# DDR3.net
KiCad netlist of a schematic drawn in Altium Designer
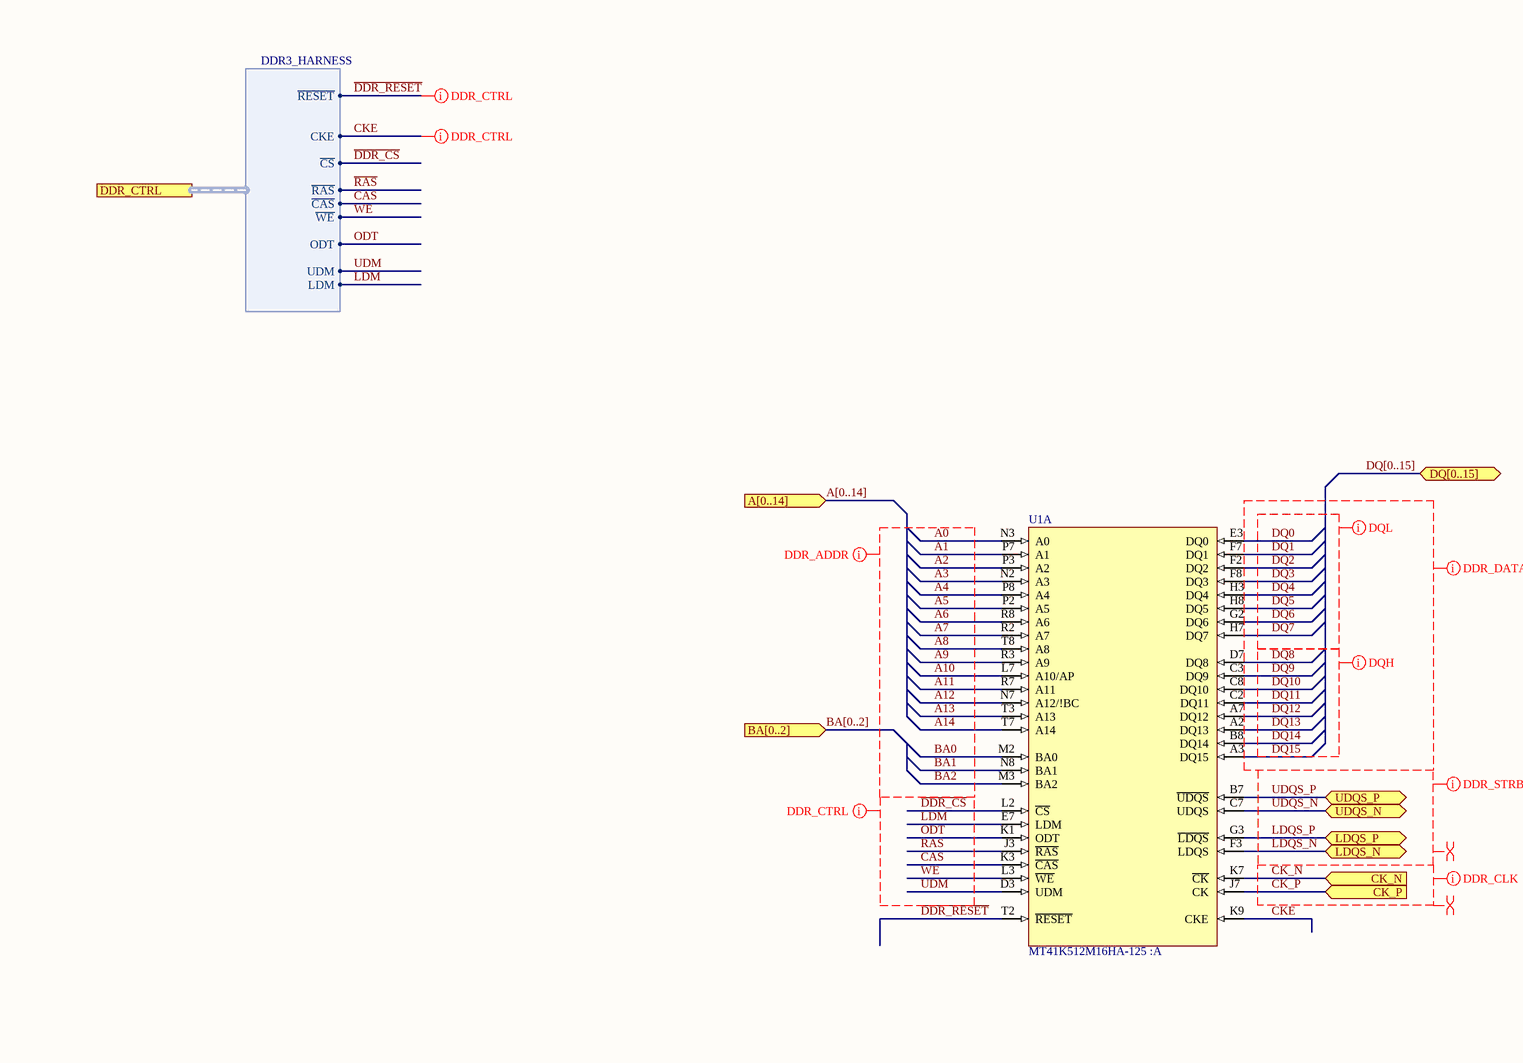
[diagram p0: DDR3.SchDoc, top left]
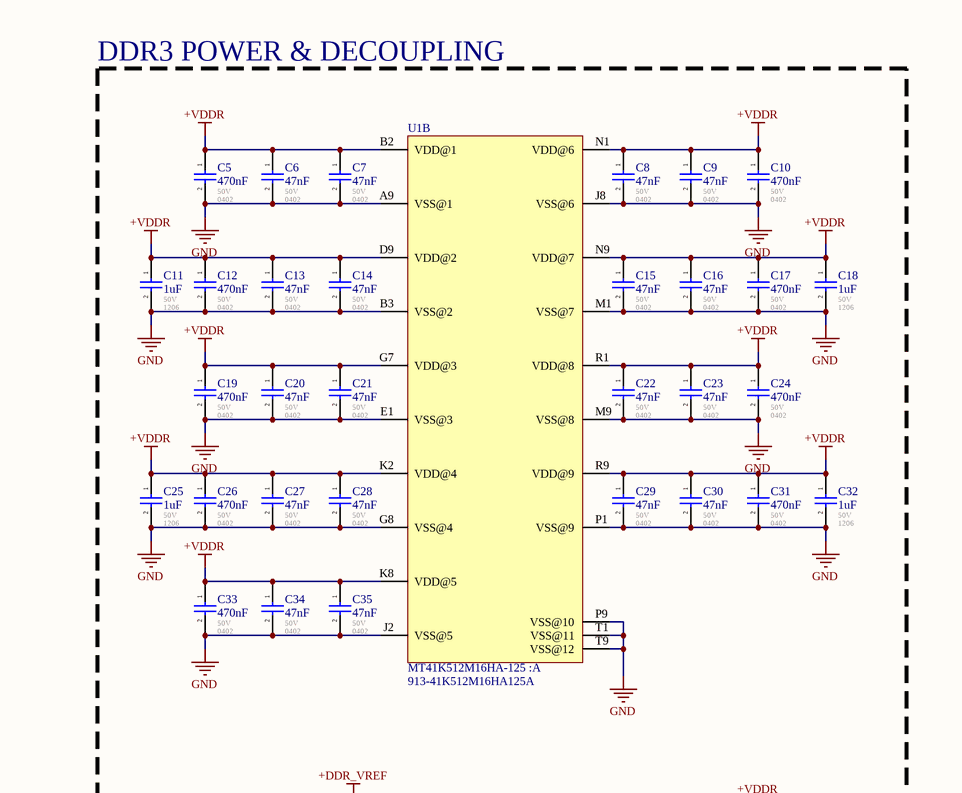
[diagram p1: DDR3.SchDoc, top right]
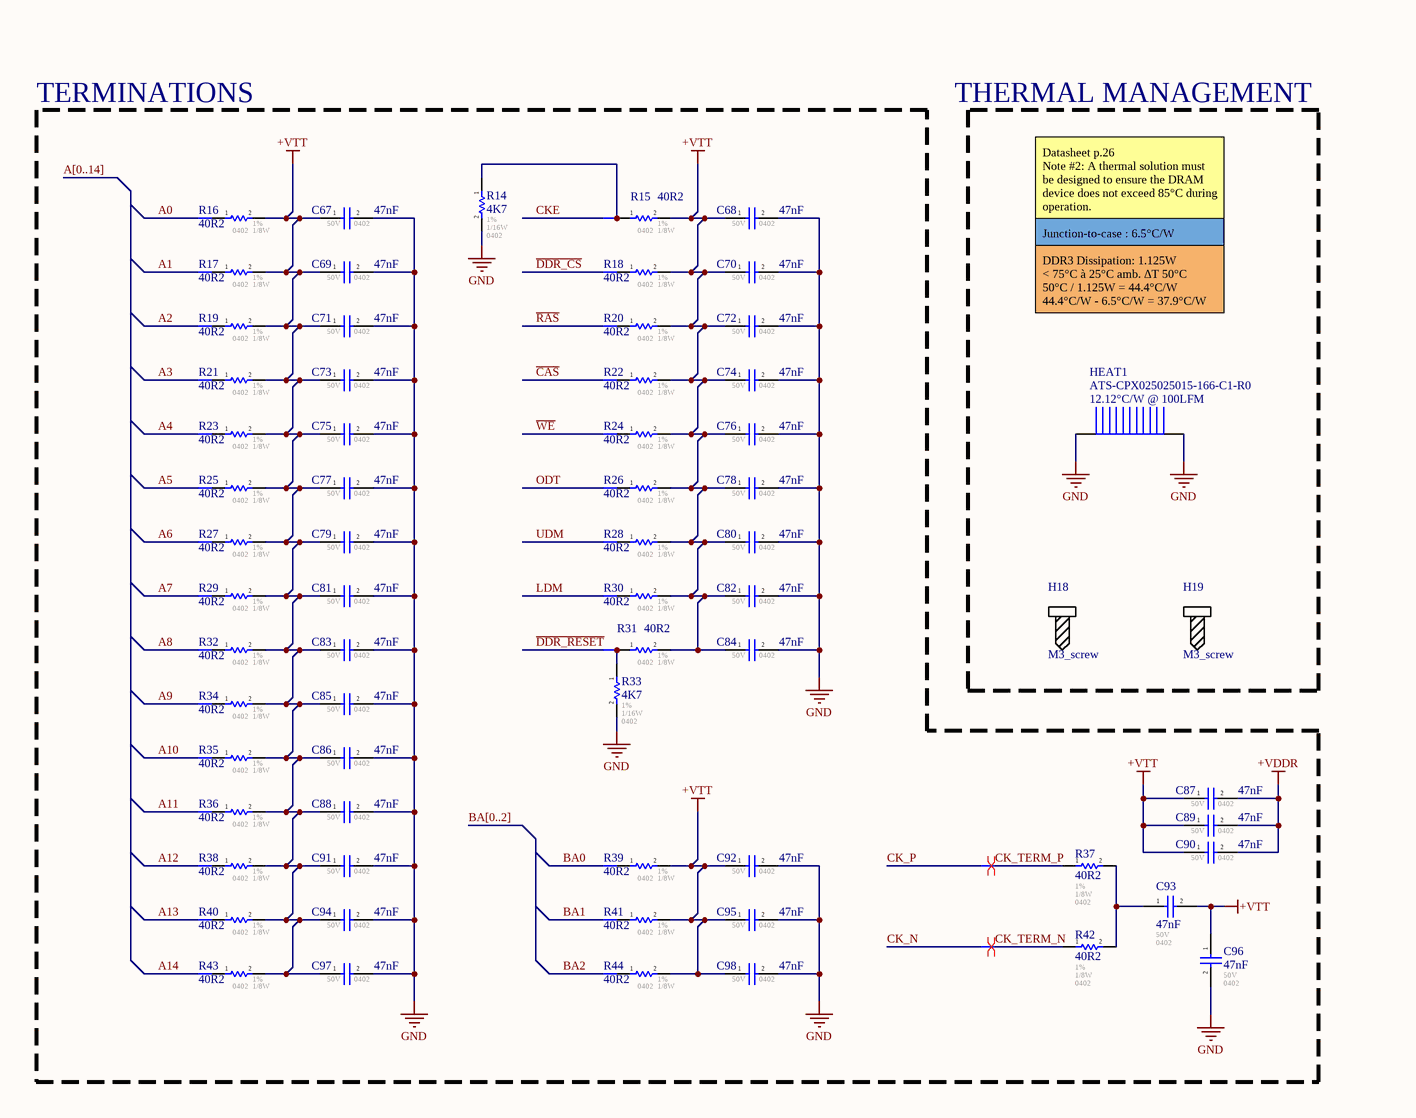
[diagram p2: DDR3.SchDoc, bottom left]
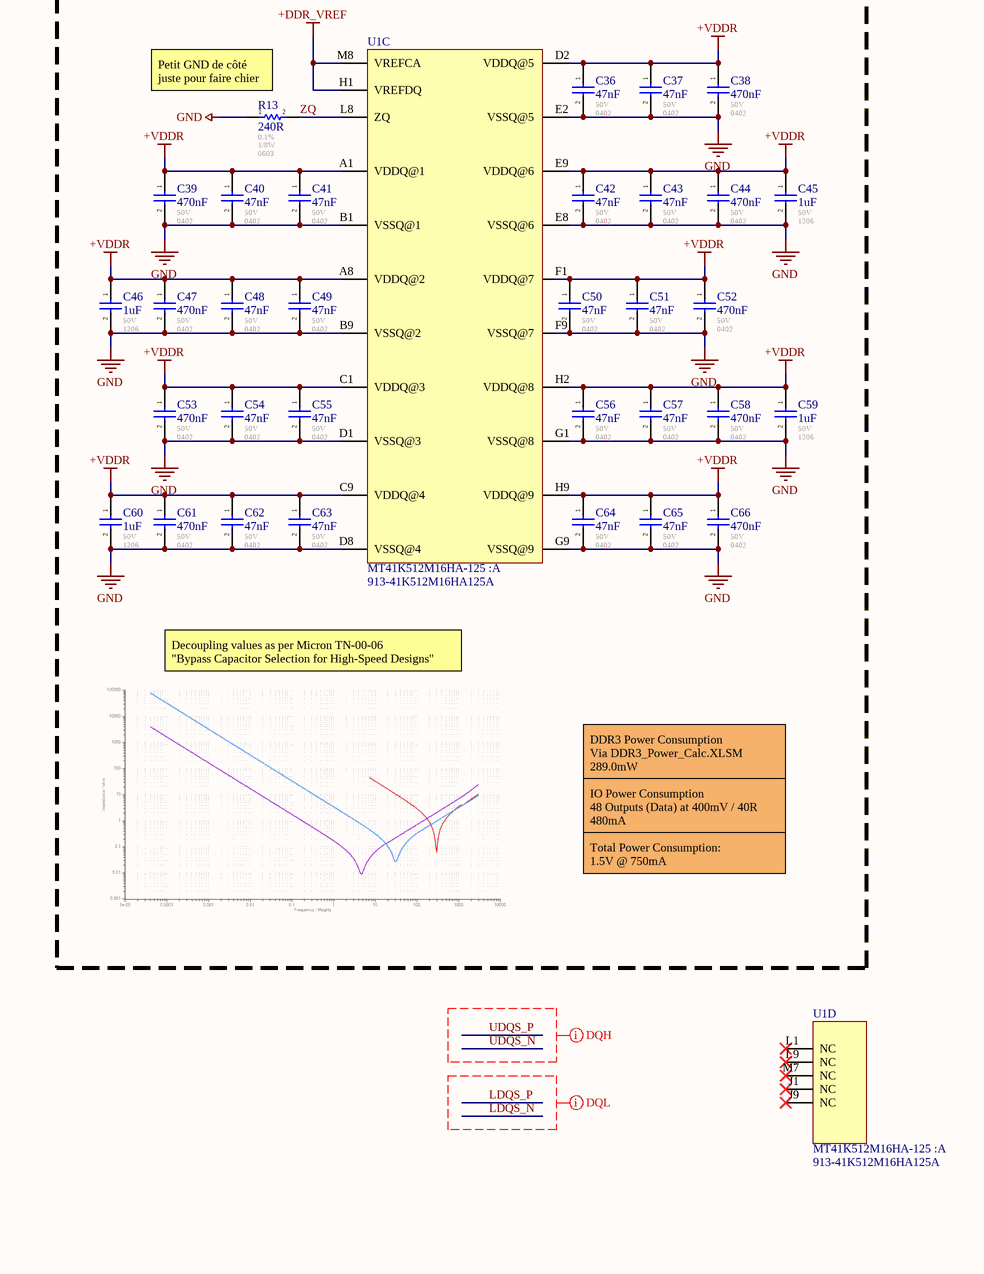
[diagram p3: DDR3.SchDoc, bottom right]

(export (version "E")
  (design (tool "Eeschema 10.0.6"))
  (components
    (comp (ref "C5")
      (value "470nF")
      (footprint "0402")
      (description "CGA3E3X7R1H474K080AB\r\n0603 470nF 10% X7R Ceramic Capacitor")
      (fields
        (field (name "MFR") "TDK")
        (field (name "PART#") "CGA3E3X7R1H474K080AB")
        (field (name "VOLTAGE - RATED") "50V")
      )
      (libsource (lib "Symbols") (part "CAP_CER"))
    )
    (comp (ref "C6")
      (value "47nF")
      (footprint "0402")
      (description "GCM155R71H473KE02J\r\n0402 47nF 10% X7R Ceramic Capacitor")
      (fields
        (field (name "MFR") "Murata")
        (field (name "PART#") "GCM155R71H473KE02J")
        (field (name "VOLTAGE - RATED") "50V")
      )
      (libsource (lib "Symbols") (part "CAP_CER"))
    )
    (comp (ref "C7")
      (value "47nF")
      (footprint "0402")
      (description "GCM155R71H473KE02J\r\n0402 47nF 10% X7R Ceramic Capacitor")
      (fields
        (field (name "MFR") "Murata")
        (field (name "PART#") "GCM155R71H473KE02J")
        (field (name "VOLTAGE - RATED") "50V")
      )
      (libsource (lib "Symbols") (part "CAP_CER"))
    )
    (comp (ref "C8")
      (value "47nF")
      (footprint "0402")
      (description "GCM155R71H473KE02J\r\n0402 47nF 10% X7R Ceramic Capacitor")
      (fields
        (field (name "MFR") "Murata")
        (field (name "PART#") "GCM155R71H473KE02J")
        (field (name "VOLTAGE - RATED") "50V")
      )
      (libsource (lib "Symbols") (part "CAP_CER"))
    )
    (comp (ref "C9")
      (value "47nF")
      (footprint "0402")
      (description "GCM155R71H473KE02J\r\n0402 47nF 10% X7R Ceramic Capacitor")
      (fields
        (field (name "MFR") "Murata")
        (field (name "PART#") "GCM155R71H473KE02J")
        (field (name "VOLTAGE - RATED") "50V")
      )
      (libsource (lib "Symbols") (part "CAP_CER"))
    )
    (comp (ref "C10")
      (value "470nF")
      (footprint "0402")
      (description "CGA3E3X7R1H474K080AB\r\n0603 470nF 10% X7R Ceramic Capacitor")
      (fields
        (field (name "MFR") "TDK")
        (field (name "PART#") "CGA3E3X7R1H474K080AB")
        (field (name "VOLTAGE - RATED") "50V")
      )
      (libsource (lib "Symbols") (part "CAP_CER"))
    )
    (comp (ref "C11")
      (value "1uF")
      (footprint "1206")
      (description "GCJ31CR71H105KA12L\r\n1206 1uF 10% X7R Ceramic Capacitor")
      (fields
        (field (name "MFR") "Murata")
        (field (name "PART#") "GCJ31CR71H105KA12L")
        (field (name "VOLTAGE - RATED") "50V")
      )
      (libsource (lib "Symbols") (part "CAP_CER"))
    )
    (comp (ref "C12")
      (value "470nF")
      (footprint "0402")
      (description "CGA3E3X7R1H474K080AB\r\n0603 470nF 10% X7R Ceramic Capacitor")
      (fields
        (field (name "MFR") "TDK")
        (field (name "PART#") "CGA3E3X7R1H474K080AB")
        (field (name "VOLTAGE - RATED") "50V")
      )
      (libsource (lib "Symbols") (part "CAP_CER"))
    )
    (comp (ref "C13")
      (value "47nF")
      (footprint "0402")
      (description "GCM155R71H473KE02J\r\n0402 47nF 10% X7R Ceramic Capacitor")
      (fields
        (field (name "MFR") "Murata")
        (field (name "PART#") "GCM155R71H473KE02J")
        (field (name "VOLTAGE - RATED") "50V")
      )
      (libsource (lib "Symbols") (part "CAP_CER"))
    )
    (comp (ref "C14")
      (value "47nF")
      (footprint "0402")
      (description "GCM155R71H473KE02J\r\n0402 47nF 10% X7R Ceramic Capacitor")
      (fields
        (field (name "MFR") "Murata")
        (field (name "PART#") "GCM155R71H473KE02J")
        (field (name "VOLTAGE - RATED") "50V")
      )
      (libsource (lib "Symbols") (part "CAP_CER"))
    )
    (comp (ref "C15")
      (value "47nF")
      (footprint "0402")
      (description "GCM155R71H473KE02J\r\n0402 47nF 10% X7R Ceramic Capacitor")
      (fields
        (field (name "MFR") "Murata")
        (field (name "PART#") "GCM155R71H473KE02J")
        (field (name "VOLTAGE - RATED") "50V")
      )
      (libsource (lib "Symbols") (part "CAP_CER"))
    )
    (comp (ref "C16")
      (value "47nF")
      (footprint "0402")
      (description "GCM155R71H473KE02J\r\n0402 47nF 10% X7R Ceramic Capacitor")
      (fields
        (field (name "MFR") "Murata")
        (field (name "PART#") "GCM155R71H473KE02J")
        (field (name "VOLTAGE - RATED") "50V")
      )
      (libsource (lib "Symbols") (part "CAP_CER"))
    )
    (comp (ref "C17")
      (value "470nF")
      (footprint "0402")
      (description "CGA3E3X7R1H474K080AB\r\n0603 470nF 10% X7R Ceramic Capacitor")
      (fields
        (field (name "MFR") "TDK")
        (field (name "PART#") "CGA3E3X7R1H474K080AB")
        (field (name "VOLTAGE - RATED") "50V")
      )
      (libsource (lib "Symbols") (part "CAP_CER"))
    )
    (comp (ref "C18")
      (value "1uF")
      (footprint "1206")
      (description "GCJ31CR71H105KA12L\r\n1206 1uF 10% X7R Ceramic Capacitor")
      (fields
        (field (name "MFR") "Murata")
        (field (name "PART#") "GCJ31CR71H105KA12L")
        (field (name "VOLTAGE - RATED") "50V")
      )
      (libsource (lib "Symbols") (part "CAP_CER"))
    )
    (comp (ref "C19")
      (value "470nF")
      (footprint "0402")
      (description "CGA3E3X7R1H474K080AB\r\n0603 470nF 10% X7R Ceramic Capacitor")
      (fields
        (field (name "MFR") "TDK")
        (field (name "PART#") "CGA3E3X7R1H474K080AB")
        (field (name "VOLTAGE - RATED") "50V")
      )
      (libsource (lib "Symbols") (part "CAP_CER"))
    )
    (comp (ref "C20")
      (value "47nF")
      (footprint "0402")
      (description "GCM155R71H473KE02J\r\n0402 47nF 10% X7R Ceramic Capacitor")
      (fields
        (field (name "MFR") "Murata")
        (field (name "PART#") "GCM155R71H473KE02J")
        (field (name "VOLTAGE - RATED") "50V")
      )
      (libsource (lib "Symbols") (part "CAP_CER"))
    )
    (comp (ref "C21")
      (value "47nF")
      (footprint "0402")
      (description "GCM155R71H473KE02J\r\n0402 47nF 10% X7R Ceramic Capacitor")
      (fields
        (field (name "MFR") "Murata")
        (field (name "PART#") "GCM155R71H473KE02J")
        (field (name "VOLTAGE - RATED") "50V")
      )
      (libsource (lib "Symbols") (part "CAP_CER"))
    )
    (comp (ref "C22")
      (value "47nF")
      (footprint "0402")
      (description "GCM155R71H473KE02J\r\n0402 47nF 10% X7R Ceramic Capacitor")
      (fields
        (field (name "MFR") "Murata")
        (field (name "PART#") "GCM155R71H473KE02J")
        (field (name "VOLTAGE - RATED") "50V")
      )
      (libsource (lib "Symbols") (part "CAP_CER"))
    )
    (comp (ref "C23")
      (value "47nF")
      (footprint "0402")
      (description "GCM155R71H473KE02J\r\n0402 47nF 10% X7R Ceramic Capacitor")
      (fields
        (field (name "MFR") "Murata")
        (field (name "PART#") "GCM155R71H473KE02J")
        (field (name "VOLTAGE - RATED") "50V")
      )
      (libsource (lib "Symbols") (part "CAP_CER"))
    )
    (comp (ref "C24")
      (value "470nF")
      (footprint "0402")
      (description "CGA3E3X7R1H474K080AB\r\n0603 470nF 10% X7R Ceramic Capacitor")
      (fields
        (field (name "MFR") "TDK")
        (field (name "PART#") "CGA3E3X7R1H474K080AB")
        (field (name "VOLTAGE - RATED") "50V")
      )
      (libsource (lib "Symbols") (part "CAP_CER"))
    )
    (comp (ref "C25")
      (value "1uF")
      (footprint "1206")
      (description "GCJ31CR71H105KA12L\r\n1206 1uF 10% X7R Ceramic Capacitor")
      (fields
        (field (name "MFR") "Murata")
        (field (name "PART#") "GCJ31CR71H105KA12L")
        (field (name "VOLTAGE - RATED") "50V")
      )
      (libsource (lib "Symbols") (part "CAP_CER"))
    )
    (comp (ref "C26")
      (value "470nF")
      (footprint "0402")
      (description "CGA3E3X7R1H474K080AB\r\n0603 470nF 10% X7R Ceramic Capacitor")
      (fields
        (field (name "MFR") "TDK")
        (field (name "PART#") "CGA3E3X7R1H474K080AB")
        (field (name "VOLTAGE - RATED") "50V")
      )
      (libsource (lib "Symbols") (part "CAP_CER"))
    )
    (comp (ref "C27")
      (value "47nF")
      (footprint "0402")
      (description "GCM155R71H473KE02J\r\n0402 47nF 10% X7R Ceramic Capacitor")
      (fields
        (field (name "MFR") "Murata")
        (field (name "PART#") "GCM155R71H473KE02J")
        (field (name "VOLTAGE - RATED") "50V")
      )
      (libsource (lib "Symbols") (part "CAP_CER"))
    )
    (comp (ref "C28")
      (value "47nF")
      (footprint "0402")
      (description "GCM155R71H473KE02J\r\n0402 47nF 10% X7R Ceramic Capacitor")
      (fields
        (field (name "MFR") "Murata")
        (field (name "PART#") "GCM155R71H473KE02J")
        (field (name "VOLTAGE - RATED") "50V")
      )
      (libsource (lib "Symbols") (part "CAP_CER"))
    )
    (comp (ref "C29")
      (value "47nF")
      (footprint "0402")
      (description "GCM155R71H473KE02J\r\n0402 47nF 10% X7R Ceramic Capacitor")
      (fields
        (field (name "MFR") "Murata")
        (field (name "PART#") "GCM155R71H473KE02J")
        (field (name "VOLTAGE - RATED") "50V")
      )
      (libsource (lib "Symbols") (part "CAP_CER"))
    )
    (comp (ref "C30")
      (value "47nF")
      (footprint "0402")
      (description "GCM155R71H473KE02J\r\n0402 47nF 10% X7R Ceramic Capacitor")
      (fields
        (field (name "MFR") "Murata")
        (field (name "PART#") "GCM155R71H473KE02J")
        (field (name "VOLTAGE - RATED") "50V")
      )
      (libsource (lib "Symbols") (part "CAP_CER"))
    )
    (comp (ref "C31")
      (value "470nF")
      (footprint "0402")
      (description "CGA3E3X7R1H474K080AB\r\n0603 470nF 10% X7R Ceramic Capacitor")
      (fields
        (field (name "MFR") "TDK")
        (field (name "PART#") "CGA3E3X7R1H474K080AB")
        (field (name "VOLTAGE - RATED") "50V")
      )
      (libsource (lib "Symbols") (part "CAP_CER"))
    )
    (comp (ref "C32")
      (value "1uF")
      (footprint "1206")
      (description "GCJ31CR71H105KA12L\r\n1206 1uF 10% X7R Ceramic Capacitor")
      (fields
        (field (name "MFR") "Murata")
        (field (name "PART#") "GCJ31CR71H105KA12L")
        (field (name "VOLTAGE - RATED") "50V")
      )
      (libsource (lib "Symbols") (part "CAP_CER"))
    )
    (comp (ref "C33")
      (value "470nF")
      (footprint "0402")
      (description "CGA3E3X7R1H474K080AB\r\n0603 470nF 10% X7R Ceramic Capacitor")
      (fields
        (field (name "MFR") "TDK")
        (field (name "PART#") "CGA3E3X7R1H474K080AB")
        (field (name "VOLTAGE - RATED") "50V")
      )
      (libsource (lib "Symbols") (part "CAP_CER"))
    )
    (comp (ref "C34")
      (value "47nF")
      (footprint "0402")
      (description "GCM155R71H473KE02J\r\n0402 47nF 10% X7R Ceramic Capacitor")
      (fields
        (field (name "MFR") "Murata")
        (field (name "PART#") "GCM155R71H473KE02J")
        (field (name "VOLTAGE - RATED") "50V")
      )
      (libsource (lib "Symbols") (part "CAP_CER"))
    )
    (comp (ref "C35")
      (value "47nF")
      (footprint "0402")
      (description "GCM155R71H473KE02J\r\n0402 47nF 10% X7R Ceramic Capacitor")
      (fields
        (field (name "MFR") "Murata")
        (field (name "PART#") "GCM155R71H473KE02J")
        (field (name "VOLTAGE - RATED") "50V")
      )
      (libsource (lib "Symbols") (part "CAP_CER"))
    )
    (comp (ref "C36")
      (value "47nF")
      (footprint "0402")
      (description "GCM155R71H473KE02J\r\n0402 47nF 10% X7R Ceramic Capacitor")
      (fields
        (field (name "MFR") "Murata")
        (field (name "PART#") "GCM155R71H473KE02J")
        (field (name "VOLTAGE - RATED") "50V")
      )
      (libsource (lib "Symbols") (part "CAP_CER"))
    )
    (comp (ref "C37")
      (value "47nF")
      (footprint "0402")
      (description "GCM155R71H473KE02J\r\n0402 47nF 10% X7R Ceramic Capacitor")
      (fields
        (field (name "MFR") "Murata")
        (field (name "PART#") "GCM155R71H473KE02J")
        (field (name "VOLTAGE - RATED") "50V")
      )
      (libsource (lib "Symbols") (part "CAP_CER"))
    )
    (comp (ref "C38")
      (value "470nF")
      (footprint "0402")
      (description "CGA3E3X7R1H474K080AB\r\n0603 470nF 10% X7R Ceramic Capacitor")
      (fields
        (field (name "MFR") "TDK")
        (field (name "PART#") "CGA3E3X7R1H474K080AB")
        (field (name "VOLTAGE - RATED") "50V")
      )
      (libsource (lib "Symbols") (part "CAP_CER"))
    )
    (comp (ref "C39")
      (value "470nF")
      (footprint "0402")
      (description "CGA3E3X7R1H474K080AB\r\n0603 470nF 10% X7R Ceramic Capacitor")
      (fields
        (field (name "MFR") "TDK")
        (field (name "PART#") "CGA3E3X7R1H474K080AB")
        (field (name "VOLTAGE - RATED") "50V")
      )
      (libsource (lib "Symbols") (part "CAP_CER"))
    )
    (comp (ref "C40")
      (value "47nF")
      (footprint "0402")
      (description "GCM155R71H473KE02J\r\n0402 47nF 10% X7R Ceramic Capacitor")
      (fields
        (field (name "MFR") "Murata")
        (field (name "PART#") "GCM155R71H473KE02J")
        (field (name "VOLTAGE - RATED") "50V")
      )
      (libsource (lib "Symbols") (part "CAP_CER"))
    )
    (comp (ref "C41")
      (value "47nF")
      (footprint "0402")
      (description "GCM155R71H473KE02J\r\n0402 47nF 10% X7R Ceramic Capacitor")
      (fields
        (field (name "MFR") "Murata")
        (field (name "PART#") "GCM155R71H473KE02J")
        (field (name "VOLTAGE - RATED") "50V")
      )
      (libsource (lib "Symbols") (part "CAP_CER"))
    )
    (comp (ref "C42")
      (value "47nF")
      (footprint "0402")
      (description "GCM155R71H473KE02J\r\n0402 47nF 10% X7R Ceramic Capacitor")
      (fields
        (field (name "MFR") "Murata")
        (field (name "PART#") "GCM155R71H473KE02J")
        (field (name "VOLTAGE - RATED") "50V")
      )
      (libsource (lib "Symbols") (part "CAP_CER"))
    )
    (comp (ref "C43")
      (value "47nF")
      (footprint "0402")
      (description "GCM155R71H473KE02J\r\n0402 47nF 10% X7R Ceramic Capacitor")
      (fields
        (field (name "MFR") "Murata")
        (field (name "PART#") "GCM155R71H473KE02J")
        (field (name "VOLTAGE - RATED") "50V")
      )
      (libsource (lib "Symbols") (part "CAP_CER"))
    )
    (comp (ref "C44")
      (value "470nF")
      (footprint "0402")
      (description "CGA3E3X7R1H474K080AB\r\n0603 470nF 10% X7R Ceramic Capacitor")
      (fields
        (field (name "MFR") "TDK")
        (field (name "PART#") "CGA3E3X7R1H474K080AB")
        (field (name "VOLTAGE - RATED") "50V")
      )
      (libsource (lib "Symbols") (part "CAP_CER"))
    )
    (comp (ref "C45")
      (value "1uF")
      (footprint "1206")
      (description "GCJ31CR71H105KA12L\r\n1206 1uF 10% X7R Ceramic Capacitor")
      (fields
        (field (name "MFR") "Murata")
        (field (name "PART#") "GCJ31CR71H105KA12L")
        (field (name "VOLTAGE - RATED") "50V")
      )
      (libsource (lib "Symbols") (part "CAP_CER"))
    )
    (comp (ref "C46")
      (value "1uF")
      (footprint "1206")
      (description "GCJ31CR71H105KA12L\r\n1206 1uF 10% X7R Ceramic Capacitor")
      (fields
        (field (name "MFR") "Murata")
        (field (name "PART#") "GCJ31CR71H105KA12L")
        (field (name "VOLTAGE - RATED") "50V")
      )
      (libsource (lib "Symbols") (part "CAP_CER"))
    )
    (comp (ref "C47")
      (value "470nF")
      (footprint "0402")
      (description "CGA3E3X7R1H474K080AB\r\n0603 470nF 10% X7R Ceramic Capacitor")
      (fields
        (field (name "MFR") "TDK")
        (field (name "PART#") "CGA3E3X7R1H474K080AB")
        (field (name "VOLTAGE - RATED") "50V")
      )
      (libsource (lib "Symbols") (part "CAP_CER"))
    )
    (comp (ref "C48")
      (value "47nF")
      (footprint "0402")
      (description "GCM155R71H473KE02J\r\n0402 47nF 10% X7R Ceramic Capacitor")
      (fields
        (field (name "MFR") "Murata")
        (field (name "PART#") "GCM155R71H473KE02J")
        (field (name "VOLTAGE - RATED") "50V")
      )
      (libsource (lib "Symbols") (part "CAP_CER"))
    )
    (comp (ref "C49")
      (value "47nF")
      (footprint "0402")
      (description "GCM155R71H473KE02J\r\n0402 47nF 10% X7R Ceramic Capacitor")
      (fields
        (field (name "MFR") "Murata")
        (field (name "PART#") "GCM155R71H473KE02J")
        (field (name "VOLTAGE - RATED") "50V")
      )
      (libsource (lib "Symbols") (part "CAP_CER"))
    )
    (comp (ref "C50")
      (value "47nF")
      (footprint "0402")
      (description "GCM155R71H473KE02J\r\n0402 47nF 10% X7R Ceramic Capacitor")
      (fields
        (field (name "MFR") "Murata")
        (field (name "PART#") "GCM155R71H473KE02J")
        (field (name "VOLTAGE - RATED") "50V")
      )
      (libsource (lib "Symbols") (part "CAP_CER"))
    )
    (comp (ref "C51")
      (value "47nF")
      (footprint "0402")
      (description "GCM155R71H473KE02J\r\n0402 47nF 10% X7R Ceramic Capacitor")
      (fields
        (field (name "MFR") "Murata")
        (field (name "PART#") "GCM155R71H473KE02J")
        (field (name "VOLTAGE - RATED") "50V")
      )
      (libsource (lib "Symbols") (part "CAP_CER"))
    )
    (comp (ref "C52")
      (value "470nF")
      (footprint "0402")
      (description "CGA3E3X7R1H474K080AB\r\n0603 470nF 10% X7R Ceramic Capacitor")
      (fields
        (field (name "MFR") "TDK")
        (field (name "PART#") "CGA3E3X7R1H474K080AB")
        (field (name "VOLTAGE - RATED") "50V")
      )
      (libsource (lib "Symbols") (part "CAP_CER"))
    )
    (comp (ref "C53")
      (value "470nF")
      (footprint "0402")
      (description "CGA3E3X7R1H474K080AB\r\n0603 470nF 10% X7R Ceramic Capacitor")
      (fields
        (field (name "MFR") "TDK")
        (field (name "PART#") "CGA3E3X7R1H474K080AB")
        (field (name "VOLTAGE - RATED") "50V")
      )
      (libsource (lib "Symbols") (part "CAP_CER"))
    )
    (comp (ref "C54")
      (value "47nF")
      (footprint "0402")
      (description "GCM155R71H473KE02J\r\n0402 47nF 10% X7R Ceramic Capacitor")
      (fields
        (field (name "MFR") "Murata")
        (field (name "PART#") "GCM155R71H473KE02J")
        (field (name "VOLTAGE - RATED") "50V")
      )
      (libsource (lib "Symbols") (part "CAP_CER"))
    )
    (comp (ref "C55")
      (value "47nF")
      (footprint "0402")
      (description "GCM155R71H473KE02J\r\n0402 47nF 10% X7R Ceramic Capacitor")
      (fields
        (field (name "MFR") "Murata")
        (field (name "PART#") "GCM155R71H473KE02J")
        (field (name "VOLTAGE - RATED") "50V")
      )
      (libsource (lib "Symbols") (part "CAP_CER"))
    )
    (comp (ref "C56")
      (value "47nF")
      (footprint "0402")
      (description "GCM155R71H473KE02J\r\n0402 47nF 10% X7R Ceramic Capacitor")
      (fields
        (field (name "MFR") "Murata")
        (field (name "PART#") "GCM155R71H473KE02J")
        (field (name "VOLTAGE - RATED") "50V")
      )
      (libsource (lib "Symbols") (part "CAP_CER"))
    )
    (comp (ref "C57")
      (value "47nF")
      (footprint "0402")
      (description "GCM155R71H473KE02J\r\n0402 47nF 10% X7R Ceramic Capacitor")
      (fields
        (field (name "MFR") "Murata")
        (field (name "PART#") "GCM155R71H473KE02J")
        (field (name "VOLTAGE - RATED") "50V")
      )
      (libsource (lib "Symbols") (part "CAP_CER"))
    )
    (comp (ref "C58")
      (value "470nF")
      (footprint "0402")
      (description "CGA3E3X7R1H474K080AB\r\n0603 470nF 10% X7R Ceramic Capacitor")
      (fields
        (field (name "MFR") "TDK")
        (field (name "PART#") "CGA3E3X7R1H474K080AB")
        (field (name "VOLTAGE - RATED") "50V")
      )
      (libsource (lib "Symbols") (part "CAP_CER"))
    )
    (comp (ref "C59")
      (value "1uF")
      (footprint "1206")
      (description "GCJ31CR71H105KA12L\r\n1206 1uF 10% X7R Ceramic Capacitor")
      (fields
        (field (name "MFR") "Murata")
        (field (name "PART#") "GCJ31CR71H105KA12L")
        (field (name "VOLTAGE - RATED") "50V")
      )
      (libsource (lib "Symbols") (part "CAP_CER"))
    )
    (comp (ref "C60")
      (value "1uF")
      (footprint "1206")
      (description "GCJ31CR71H105KA12L\r\n1206 1uF 10% X7R Ceramic Capacitor")
      (fields
        (field (name "MFR") "Murata")
        (field (name "PART#") "GCJ31CR71H105KA12L")
        (field (name "VOLTAGE - RATED") "50V")
      )
      (libsource (lib "Symbols") (part "CAP_CER"))
    )
    (comp (ref "C61")
      (value "470nF")
      (footprint "0402")
      (description "CGA3E3X7R1H474K080AB\r\n0603 470nF 10% X7R Ceramic Capacitor")
      (fields
        (field (name "MFR") "TDK")
        (field (name "PART#") "CGA3E3X7R1H474K080AB")
        (field (name "VOLTAGE - RATED") "50V")
      )
      (libsource (lib "Symbols") (part "CAP_CER"))
    )
    (comp (ref "C62")
      (value "47nF")
      (footprint "0402")
      (description "GCM155R71H473KE02J\r\n0402 47nF 10% X7R Ceramic Capacitor")
      (fields
        (field (name "MFR") "Murata")
        (field (name "PART#") "GCM155R71H473KE02J")
        (field (name "VOLTAGE - RATED") "50V")
      )
      (libsource (lib "Symbols") (part "CAP_CER"))
    )
    (comp (ref "C63")
      (value "47nF")
      (footprint "0402")
      (description "GCM155R71H473KE02J\r\n0402 47nF 10% X7R Ceramic Capacitor")
      (fields
        (field (name "MFR") "Murata")
        (field (name "PART#") "GCM155R71H473KE02J")
        (field (name "VOLTAGE - RATED") "50V")
      )
      (libsource (lib "Symbols") (part "CAP_CER"))
    )
    (comp (ref "C64")
      (value "47nF")
      (footprint "0402")
      (description "GCM155R71H473KE02J\r\n0402 47nF 10% X7R Ceramic Capacitor")
      (fields
        (field (name "MFR") "Murata")
        (field (name "PART#") "GCM155R71H473KE02J")
        (field (name "VOLTAGE - RATED") "50V")
      )
      (libsource (lib "Symbols") (part "CAP_CER"))
    )
    (comp (ref "C65")
      (value "47nF")
      (footprint "0402")
      (description "GCM155R71H473KE02J\r\n0402 47nF 10% X7R Ceramic Capacitor")
      (fields
        (field (name "MFR") "Murata")
        (field (name "PART#") "GCM155R71H473KE02J")
        (field (name "VOLTAGE - RATED") "50V")
      )
      (libsource (lib "Symbols") (part "CAP_CER"))
    )
    (comp (ref "C66")
      (value "470nF")
      (footprint "0402")
      (description "CGA3E3X7R1H474K080AB\r\n0603 470nF 10% X7R Ceramic Capacitor")
      (fields
        (field (name "MFR") "TDK")
        (field (name "PART#") "CGA3E3X7R1H474K080AB")
        (field (name "VOLTAGE - RATED") "50V")
      )
      (libsource (lib "Symbols") (part "CAP_CER"))
    )
    (comp (ref "C67")
      (value "47nF")
      (footprint "0402")
      (description "GCM155R71H473KE02J\r\n0402 47nF 10% X7R Ceramic Capacitor")
      (fields
        (field (name "MFR") "Murata")
        (field (name "PART#") "GCM155R71H473KE02J")
        (field (name "VOLTAGE - RATED") "50V")
      )
      (libsource (lib "Symbols") (part "CAP_CER"))
    )
    (comp (ref "C68")
      (value "47nF")
      (footprint "0402")
      (description "GCM155R71H473KE02J\r\n0402 47nF 10% X7R Ceramic Capacitor")
      (fields
        (field (name "MFR") "Murata")
        (field (name "PART#") "GCM155R71H473KE02J")
        (field (name "VOLTAGE - RATED") "50V")
      )
      (libsource (lib "Symbols") (part "CAP_CER"))
    )
    (comp (ref "C69")
      (value "47nF")
      (footprint "0402")
      (description "GCM155R71H473KE02J\r\n0402 47nF 10% X7R Ceramic Capacitor")
      (fields
        (field (name "MFR") "Murata")
        (field (name "PART#") "GCM155R71H473KE02J")
        (field (name "VOLTAGE - RATED") "50V")
      )
      (libsource (lib "Symbols") (part "CAP_CER"))
    )
    (comp (ref "C70")
      (value "47nF")
      (footprint "0402")
      (description "GCM155R71H473KE02J\r\n0402 47nF 10% X7R Ceramic Capacitor")
      (fields
        (field (name "MFR") "Murata")
        (field (name "PART#") "GCM155R71H473KE02J")
        (field (name "VOLTAGE - RATED") "50V")
      )
      (libsource (lib "Symbols") (part "CAP_CER"))
    )
    (comp (ref "C71")
      (value "47nF")
      (footprint "0402")
      (description "GCM155R71H473KE02J\r\n0402 47nF 10% X7R Ceramic Capacitor")
      (fields
        (field (name "MFR") "Murata")
        (field (name "PART#") "GCM155R71H473KE02J")
        (field (name "VOLTAGE - RATED") "50V")
      )
      (libsource (lib "Symbols") (part "CAP_CER"))
    )
    (comp (ref "C72")
      (value "47nF")
      (footprint "0402")
      (description "GCM155R71H473KE02J\r\n0402 47nF 10% X7R Ceramic Capacitor")
      (fields
        (field (name "MFR") "Murata")
        (field (name "PART#") "GCM155R71H473KE02J")
        (field (name "VOLTAGE - RATED") "50V")
      )
      (libsource (lib "Symbols") (part "CAP_CER"))
    )
    (comp (ref "C73")
      (value "47nF")
      (footprint "0402")
      (description "GCM155R71H473KE02J\r\n0402 47nF 10% X7R Ceramic Capacitor")
      (fields
        (field (name "MFR") "Murata")
        (field (name "PART#") "GCM155R71H473KE02J")
        (field (name "VOLTAGE - RATED") "50V")
      )
      (libsource (lib "Symbols") (part "CAP_CER"))
    )
    (comp (ref "C74")
      (value "47nF")
      (footprint "0402")
      (description "GCM155R71H473KE02J\r\n0402 47nF 10% X7R Ceramic Capacitor")
      (fields
        (field (name "MFR") "Murata")
        (field (name "PART#") "GCM155R71H473KE02J")
        (field (name "VOLTAGE - RATED") "50V")
      )
      (libsource (lib "Symbols") (part "CAP_CER"))
    )
    (comp (ref "C75")
      (value "47nF")
      (footprint "0402")
      (description "GCM155R71H473KE02J\r\n0402 47nF 10% X7R Ceramic Capacitor")
      (fields
        (field (name "MFR") "Murata")
        (field (name "PART#") "GCM155R71H473KE02J")
        (field (name "VOLTAGE - RATED") "50V")
      )
      (libsource (lib "Symbols") (part "CAP_CER"))
    )
    (comp (ref "C76")
      (value "47nF")
      (footprint "0402")
      (description "GCM155R71H473KE02J\r\n0402 47nF 10% X7R Ceramic Capacitor")
      (fields
        (field (name "MFR") "Murata")
        (field (name "PART#") "GCM155R71H473KE02J")
        (field (name "VOLTAGE - RATED") "50V")
      )
      (libsource (lib "Symbols") (part "CAP_CER"))
    )
    (comp (ref "C77")
      (value "47nF")
      (footprint "0402")
      (description "GCM155R71H473KE02J\r\n0402 47nF 10% X7R Ceramic Capacitor")
      (fields
        (field (name "MFR") "Murata")
        (field (name "PART#") "GCM155R71H473KE02J")
        (field (name "VOLTAGE - RATED") "50V")
      )
      (libsource (lib "Symbols") (part "CAP_CER"))
    )
    (comp (ref "C78")
      (value "47nF")
      (footprint "0402")
      (description "GCM155R71H473KE02J\r\n0402 47nF 10% X7R Ceramic Capacitor")
      (fields
        (field (name "MFR") "Murata")
        (field (name "PART#") "GCM155R71H473KE02J")
        (field (name "VOLTAGE - RATED") "50V")
      )
      (libsource (lib "Symbols") (part "CAP_CER"))
    )
    (comp (ref "C79")
      (value "47nF")
      (footprint "0402")
      (description "GCM155R71H473KE02J\r\n0402 47nF 10% X7R Ceramic Capacitor")
      (fields
        (field (name "MFR") "Murata")
        (field (name "PART#") "GCM155R71H473KE02J")
        (field (name "VOLTAGE - RATED") "50V")
      )
      (libsource (lib "Symbols") (part "CAP_CER"))
    )
    (comp (ref "C80")
      (value "47nF")
      (footprint "0402")
      (description "GCM155R71H473KE02J\r\n0402 47nF 10% X7R Ceramic Capacitor")
      (fields
        (field (name "MFR") "Murata")
        (field (name "PART#") "GCM155R71H473KE02J")
        (field (name "VOLTAGE - RATED") "50V")
      )
      (libsource (lib "Symbols") (part "CAP_CER"))
    )
    (comp (ref "C81")
      (value "47nF")
      (footprint "0402")
      (description "GCM155R71H473KE02J\r\n0402 47nF 10% X7R Ceramic Capacitor")
      (fields
        (field (name "MFR") "Murata")
        (field (name "PART#") "GCM155R71H473KE02J")
        (field (name "VOLTAGE - RATED") "50V")
      )
      (libsource (lib "Symbols") (part "CAP_CER"))
    )
    (comp (ref "C82")
      (value "47nF")
      (footprint "0402")
      (description "GCM155R71H473KE02J\r\n0402 47nF 10% X7R Ceramic Capacitor")
      (fields
        (field (name "MFR") "Murata")
        (field (name "PART#") "GCM155R71H473KE02J")
        (field (name "VOLTAGE - RATED") "50V")
      )
      (libsource (lib "Symbols") (part "CAP_CER"))
    )
    (comp (ref "C83")
      (value "47nF")
      (footprint "0402")
      (description "GCM155R71H473KE02J\r\n0402 47nF 10% X7R Ceramic Capacitor")
      (fields
        (field (name "MFR") "Murata")
        (field (name "PART#") "GCM155R71H473KE02J")
        (field (name "VOLTAGE - RATED") "50V")
      )
      (libsource (lib "Symbols") (part "CAP_CER"))
    )
    (comp (ref "C84")
      (value "47nF")
      (footprint "0402")
      (description "GCM155R71H473KE02J\r\n0402 47nF 10% X7R Ceramic Capacitor")
      (fields
        (field (name "MFR") "Murata")
        (field (name "PART#") "GCM155R71H473KE02J")
        (field (name "VOLTAGE - RATED") "50V")
      )
      (libsource (lib "Symbols") (part "CAP_CER"))
    )
    (comp (ref "C85")
      (value "47nF")
      (footprint "0402")
      (description "GCM155R71H473KE02J\r\n0402 47nF 10% X7R Ceramic Capacitor")
      (fields
        (field (name "MFR") "Murata")
        (field (name "PART#") "GCM155R71H473KE02J")
        (field (name "VOLTAGE - RATED") "50V")
      )
      (libsource (lib "Symbols") (part "CAP_CER"))
    )
    (comp (ref "C86")
      (value "47nF")
      (footprint "0402")
      (description "GCM155R71H473KE02J\r\n0402 47nF 10% X7R Ceramic Capacitor")
      (fields
        (field (name "MFR") "Murata")
        (field (name "PART#") "GCM155R71H473KE02J")
        (field (name "VOLTAGE - RATED") "50V")
      )
      (libsource (lib "Symbols") (part "CAP_CER"))
    )
    (comp (ref "C87")
      (value "47nF")
      (footprint "0402")
      (description "GCM155R71H473KE02J\r\n0402 47nF 10% X7R Ceramic Capacitor")
      (fields
        (field (name "MFR") "Murata")
        (field (name "PART#") "GCM155R71H473KE02J")
        (field (name "VOLTAGE - RATED") "50V")
      )
      (libsource (lib "Symbols") (part "CAP_CER"))
    )
    (comp (ref "C88")
      (value "47nF")
      (footprint "0402")
      (description "GCM155R71H473KE02J\r\n0402 47nF 10% X7R Ceramic Capacitor")
      (fields
        (field (name "MFR") "Murata")
        (field (name "PART#") "GCM155R71H473KE02J")
        (field (name "VOLTAGE - RATED") "50V")
      )
      (libsource (lib "Symbols") (part "CAP_CER"))
    )
    (comp (ref "C89")
      (value "47nF")
      (footprint "0402")
      (description "GCM155R71H473KE02J\r\n0402 47nF 10% X7R Ceramic Capacitor")
      (fields
        (field (name "MFR") "Murata")
        (field (name "PART#") "GCM155R71H473KE02J")
        (field (name "VOLTAGE - RATED") "50V")
      )
      (libsource (lib "Symbols") (part "CAP_CER"))
    )
    (comp (ref "C90")
      (value "47nF")
      (footprint "0402")
      (description "GCM155R71H473KE02J\r\n0402 47nF 10% X7R Ceramic Capacitor")
      (fields
        (field (name "MFR") "Murata")
        (field (name "PART#") "GCM155R71H473KE02J")
        (field (name "VOLTAGE - RATED") "50V")
      )
      (libsource (lib "Symbols") (part "CAP_CER"))
    )
    (comp (ref "C91")
      (value "47nF")
      (footprint "0402")
      (description "GCM155R71H473KE02J\r\n0402 47nF 10% X7R Ceramic Capacitor")
      (fields
        (field (name "MFR") "Murata")
        (field (name "PART#") "GCM155R71H473KE02J")
        (field (name "VOLTAGE - RATED") "50V")
      )
      (libsource (lib "Symbols") (part "CAP_CER"))
    )
    (comp (ref "C92")
      (value "47nF")
      (footprint "0402")
      (description "GCM155R71H473KE02J\r\n0402 47nF 10% X7R Ceramic Capacitor")
      (fields
        (field (name "MFR") "Murata")
        (field (name "PART#") "GCM155R71H473KE02J")
        (field (name "VOLTAGE - RATED") "50V")
      )
      (libsource (lib "Symbols") (part "CAP_CER"))
    )
    (comp (ref "C93")
      (value "47nF")
      (footprint "0402")
      (description "GCM155R71H473KE02J\r\n0402 47nF 10% X7R Ceramic Capacitor")
      (fields
        (field (name "MFR") "Murata")
        (field (name "PART#") "GCM155R71H473KE02J")
        (field (name "VOLTAGE - RATED") "50V")
      )
      (libsource (lib "Symbols") (part "CAP_CER"))
    )
    (comp (ref "C94")
      (value "47nF")
      (footprint "0402")
      (description "GCM155R71H473KE02J\r\n0402 47nF 10% X7R Ceramic Capacitor")
      (fields
        (field (name "MFR") "Murata")
        (field (name "PART#") "GCM155R71H473KE02J")
        (field (name "VOLTAGE - RATED") "50V")
      )
      (libsource (lib "Symbols") (part "CAP_CER"))
    )
    (comp (ref "C95")
      (value "47nF")
      (footprint "0402")
      (description "GCM155R71H473KE02J\r\n0402 47nF 10% X7R Ceramic Capacitor")
      (fields
        (field (name "MFR") "Murata")
        (field (name "PART#") "GCM155R71H473KE02J")
        (field (name "VOLTAGE - RATED") "50V")
      )
      (libsource (lib "Symbols") (part "CAP_CER"))
    )
    (comp (ref "C96")
      (value "47nF")
      (footprint "0402")
      (description "GCM155R71H473KE02J\r\n0402 47nF 10% X7R Ceramic Capacitor")
      (fields
        (field (name "MFR") "Murata")
        (field (name "PART#") "GCM155R71H473KE02J")
        (field (name "VOLTAGE - RATED") "50V")
      )
      (libsource (lib "Symbols") (part "CAP_CER"))
    )
    (comp (ref "C97")
      (value "47nF")
      (footprint "0402")
      (description "GCM155R71H473KE02J\r\n0402 47nF 10% X7R Ceramic Capacitor")
      (fields
        (field (name "MFR") "Murata")
        (field (name "PART#") "GCM155R71H473KE02J")
        (field (name "VOLTAGE - RATED") "50V")
      )
      (libsource (lib "Symbols") (part "CAP_CER"))
    )
    (comp (ref "C98")
      (value "47nF")
      (footprint "0402")
      (description "GCM155R71H473KE02J\r\n0402 47nF 10% X7R Ceramic Capacitor")
      (fields
        (field (name "MFR") "Murata")
        (field (name "PART#") "GCM155R71H473KE02J")
        (field (name "VOLTAGE - RATED") "50V")
      )
      (libsource (lib "Symbols") (part "CAP_CER"))
    )
    (comp (ref "H18") (value "M3_screw") (libsource (lib "Misc") (part "M3_SCREW")))
    (comp (ref "H19") (value "M3_screw") (libsource (lib "Misc") (part "M3_SCREW")))
    (comp (ref "HEAT1")
      (value "ATS-CPX025025015-166-C1-R0")
      (footprint "ATS-CPX025025015-166-C1-R0")
      (description "Heatsink Aluminium")
      (fields
        (field (name "MFR") "Advanced Thermal Solutions Inc.")
        (field (name "THERMAL RESISTANCE") "12.12°C/W @ 100LFM")
      )
      (libsource (lib "Misc") (part "HEATSINK_ATS-CPX025025015-166-C1-R0"))
    )
    (comp (ref "NT1")
      (value "Net Tie")
      (footprint "NETTIE_9")
      (libsource (lib "Symbols") (part "NET_TIE_SMALL"))
    )
    (comp (ref "NT2")
      (value "Net Tie")
      (footprint "NETTIE_9")
      (libsource (lib "Symbols") (part "NET_TIE_SMALL"))
    )
    (comp (ref "NT3")
      (value "Net Tie")
      (footprint "NETTIE_9")
      (libsource (lib "Symbols") (part "NET_TIE_SMALL"))
    )
    (comp (ref "NT4")
      (value "Net Tie")
      (footprint "NETTIE_9")
      (libsource (lib "Symbols") (part "NET_TIE_SMALL"))
    )
    (comp (ref "NT5")
      (value "Net Tie")
      (footprint "NETTIE_9")
      (libsource (lib "Symbols") (part "NET_TIE_SMALL"))
    )
    (comp (ref "NT6")
      (value "Net Tie")
      (footprint "NETTIE_9")
      (libsource (lib "Symbols") (part "NET_TIE_SMALL"))
    )
    (comp (ref "NT7")
      (value "Net Tie")
      (footprint "NETTIE_9")
      (libsource (lib "Symbols") (part "NET_TIE_SMALL"))
    )
    (comp (ref "NT8")
      (value "Net Tie")
      (footprint "NETTIE_9")
      (libsource (lib "Symbols") (part "NET_TIE_SMALL"))
    )
    (comp (ref "NT9")
      (value "Net Tie")
      (footprint "NETTIE_9")
      (libsource (lib "Symbols") (part "NET_TIE_SMALL"))
    )
    (comp (ref "NT10")
      (value "Net Tie")
      (footprint "NETTIE_9")
      (libsource (lib "Symbols") (part "NET_TIE_SMALL"))
    )
    (comp (ref "NT11")
      (value "Net Tie")
      (footprint "NETTIE_9")
      (libsource (lib "Symbols") (part "NET_TIE_SMALL"))
    )
    (comp (ref "NT12")
      (value "Net Tie")
      (footprint "NETTIE_9")
      (libsource (lib "Symbols") (part "NET_TIE_SMALL"))
    )
    (comp (ref "NT13")
      (value "Net Tie")
      (footprint "NETTIE_9")
      (libsource (lib "Symbols") (part "NET_TIE_SMALL"))
    )
    (comp (ref "NT14")
      (value "Net Tie")
      (footprint "NETTIE_9")
      (libsource (lib "Symbols") (part "NET_TIE_SMALL"))
    )
    (comp (ref "NT15")
      (value "Net Tie")
      (footprint "NETTIE_9")
      (libsource (lib "Symbols") (part "NET_TIE_SMALL"))
    )
    (comp (ref "NT16")
      (value "Net Tie")
      (footprint "NETTIE_9")
      (libsource (lib "Symbols") (part "NET_TIE_SMALL"))
    )
    (comp (ref "NT17")
      (value "Net Tie")
      (footprint "NETTIE_9")
      (libsource (lib "Symbols") (part "NET_TIE_SMALL"))
    )
    (comp (ref "NT18")
      (value "Net Tie")
      (footprint "NETTIE_9")
      (libsource (lib "Symbols") (part "NET_TIE_SMALL"))
    )
    (comp (ref "NT19")
      (value "Net Tie")
      (footprint "NETTIE_9")
      (libsource (lib "Symbols") (part "NET_TIE_SMALL"))
    )
    (comp (ref "NT20")
      (value "Net Tie")
      (footprint "NETTIE_9")
      (libsource (lib "Symbols") (part "NET_TIE_SMALL"))
    )
    (comp (ref "NT21")
      (value "Net Tie")
      (footprint "NETTIE_9")
      (libsource (lib "Symbols") (part "NET_TIE_SMALL"))
    )
    (comp (ref "NT22")
      (value "Net Tie")
      (footprint "NETTIE_9")
      (libsource (lib "Symbols") (part "NET_TIE_SMALL"))
    )
    (comp (ref "NT23")
      (value "Net Tie")
      (footprint "NETTIE_9")
      (libsource (lib "Symbols") (part "NET_TIE_SMALL"))
    )
    (comp (ref "NT24")
      (value "Net Tie")
      (footprint "NETTIE_9")
      (libsource (lib "Symbols") (part "NET_TIE_SMALL"))
    )
    (comp (ref "NT25")
      (value "Net Tie")
      (footprint "NETTIE_9")
      (libsource (lib "Symbols") (part "NET_TIE_SMALL"))
    )
    (comp (ref "NT26")
      (value "Net Tie")
      (footprint "NETTIE_9")
      (libsource (lib "Symbols") (part "NET_TIE_SMALL"))
    )
    (comp (ref "NT27")
      (value "Net Tie")
      (footprint "NETTIE_9")
      (libsource (lib "Symbols") (part "NET_TIE_SMALL"))
    )
    (comp (ref "NT28")
      (value "Net Tie")
      (footprint "NETTIE_9")
      (libsource (lib "Symbols") (part "NET_TIE_SMALL"))
    )
    (comp (ref "NT29")
      (value "Net Tie")
      (footprint "NETTIE_9")
      (libsource (lib "Symbols") (part "NET_TIE_SMALL"))
    )
    (comp (ref "R13")
      (value "240R")
      (footprint "RES_0603")
      (fields
        (field (name "TOLERANCE") "0.1%")
        (field (name "POWER") "1/8W")
        (field (name "PACKAGE / CASE") "0603")
      )
      (libsource (lib "Symbols") (part "RESISTOR"))
    )
    (comp (ref "R14")
      (value "4K7")
      (footprint "RES_0402")
      (fields
        (field (name "TOLERANCE") "1%")
        (field (name "POWER") "1/16W")
        (field (name "PACKAGE / CASE") "0402")
      )
      (libsource (lib "Symbols") (part "RESISTOR"))
    )
    (comp (ref "R15")
      (value "40R2")
      (footprint "RES_0402")
      (fields
        (field (name "TOLERANCE") "1%")
        (field (name "POWER") "1/8W")
        (field (name "PACKAGE / CASE") "0402")
      )
      (libsource (lib "Symbols") (part "RESISTOR"))
    )
    (comp (ref "R16")
      (value "40R2")
      (footprint "RES_0402")
      (fields
        (field (name "TOLERANCE") "1%")
        (field (name "POWER") "1/8W")
        (field (name "PACKAGE / CASE") "0402")
      )
      (libsource (lib "Symbols") (part "RESISTOR"))
    )
    (comp (ref "R17")
      (value "40R2")
      (footprint "RES_0402")
      (fields
        (field (name "TOLERANCE") "1%")
        (field (name "POWER") "1/8W")
        (field (name "PACKAGE / CASE") "0402")
      )
      (libsource (lib "Symbols") (part "RESISTOR"))
    )
    (comp (ref "R18")
      (value "40R2")
      (footprint "RES_0402")
      (fields
        (field (name "TOLERANCE") "1%")
        (field (name "POWER") "1/8W")
        (field (name "PACKAGE / CASE") "0402")
      )
      (libsource (lib "Symbols") (part "RESISTOR"))
    )
    (comp (ref "R19")
      (value "40R2")
      (footprint "RES_0402")
      (fields
        (field (name "TOLERANCE") "1%")
        (field (name "POWER") "1/8W")
        (field (name "PACKAGE / CASE") "0402")
      )
      (libsource (lib "Symbols") (part "RESISTOR"))
    )
    (comp (ref "R20")
      (value "40R2")
      (footprint "RES_0402")
      (fields
        (field (name "TOLERANCE") "1%")
        (field (name "POWER") "1/8W")
        (field (name "PACKAGE / CASE") "0402")
      )
      (libsource (lib "Symbols") (part "RESISTOR"))
    )
    (comp (ref "R21")
      (value "40R2")
      (footprint "RES_0402")
      (fields
        (field (name "TOLERANCE") "1%")
        (field (name "POWER") "1/8W")
        (field (name "PACKAGE / CASE") "0402")
      )
      (libsource (lib "Symbols") (part "RESISTOR"))
    )
    (comp (ref "R22")
      (value "40R2")
      (footprint "RES_0402")
      (fields
        (field (name "TOLERANCE") "1%")
        (field (name "POWER") "1/8W")
        (field (name "PACKAGE / CASE") "0402")
      )
      (libsource (lib "Symbols") (part "RESISTOR"))
    )
    (comp (ref "R23")
      (value "40R2")
      (footprint "RES_0402")
      (fields
        (field (name "TOLERANCE") "1%")
        (field (name "POWER") "1/8W")
        (field (name "PACKAGE / CASE") "0402")
      )
      (libsource (lib "Symbols") (part "RESISTOR"))
    )
    (comp (ref "R24")
      (value "40R2")
      (footprint "RES_0402")
      (fields
        (field (name "TOLERANCE") "1%")
        (field (name "POWER") "1/8W")
        (field (name "PACKAGE / CASE") "0402")
      )
      (libsource (lib "Symbols") (part "RESISTOR"))
    )
    (comp (ref "R25")
      (value "40R2")
      (footprint "RES_0402")
      (fields
        (field (name "TOLERANCE") "1%")
        (field (name "POWER") "1/8W")
        (field (name "PACKAGE / CASE") "0402")
      )
      (libsource (lib "Symbols") (part "RESISTOR"))
    )
    (comp (ref "R26")
      (value "40R2")
      (footprint "RES_0402")
      (fields
        (field (name "TOLERANCE") "1%")
        (field (name "POWER") "1/8W")
        (field (name "PACKAGE / CASE") "0402")
      )
      (libsource (lib "Symbols") (part "RESISTOR"))
    )
    (comp (ref "R27")
      (value "40R2")
      (footprint "RES_0402")
      (fields
        (field (name "TOLERANCE") "1%")
        (field (name "POWER") "1/8W")
        (field (name "PACKAGE / CASE") "0402")
      )
      (libsource (lib "Symbols") (part "RESISTOR"))
    )
    (comp (ref "R28")
      (value "40R2")
      (footprint "RES_0402")
      (fields
        (field (name "TOLERANCE") "1%")
        (field (name "POWER") "1/8W")
        (field (name "PACKAGE / CASE") "0402")
      )
      (libsource (lib "Symbols") (part "RESISTOR"))
    )
    (comp (ref "R29")
      (value "40R2")
      (footprint "RES_0402")
      (fields
        (field (name "TOLERANCE") "1%")
        (field (name "POWER") "1/8W")
        (field (name "PACKAGE / CASE") "0402")
      )
      (libsource (lib "Symbols") (part "RESISTOR"))
    )
    (comp (ref "R30")
      (value "40R2")
      (footprint "RES_0402")
      (fields
        (field (name "TOLERANCE") "1%")
        (field (name "POWER") "1/8W")
        (field (name "PACKAGE / CASE") "0402")
      )
      (libsource (lib "Symbols") (part "RESISTOR"))
    )
    (comp (ref "R31")
      (value "40R2")
      (footprint "RES_0402")
      (fields
        (field (name "TOLERANCE") "1%")
        (field (name "POWER") "1/8W")
        (field (name "PACKAGE / CASE") "0402")
      )
      (libsource (lib "Symbols") (part "RESISTOR"))
    )
    (comp (ref "R32")
      (value "40R2")
      (footprint "RES_0402")
      (fields
        (field (name "TOLERANCE") "1%")
        (field (name "POWER") "1/8W")
        (field (name "PACKAGE / CASE") "0402")
      )
      (libsource (lib "Symbols") (part "RESISTOR"))
    )
    (comp (ref "R33")
      (value "4K7")
      (footprint "RES_0402")
      (fields
        (field (name "TOLERANCE") "1%")
        (field (name "POWER") "1/16W")
        (field (name "PACKAGE / CASE") "0402")
      )
      (libsource (lib "Symbols") (part "RESISTOR"))
    )
    (comp (ref "R34")
      (value "40R2")
      (footprint "RES_0402")
      (fields
        (field (name "TOLERANCE") "1%")
        (field (name "POWER") "1/8W")
        (field (name "PACKAGE / CASE") "0402")
      )
      (libsource (lib "Symbols") (part "RESISTOR"))
    )
    (comp (ref "R35")
      (value "40R2")
      (footprint "RES_0402")
      (fields
        (field (name "TOLERANCE") "1%")
        (field (name "POWER") "1/8W")
        (field (name "PACKAGE / CASE") "0402")
      )
      (libsource (lib "Symbols") (part "RESISTOR"))
    )
    (comp (ref "R36")
      (value "40R2")
      (footprint "RES_0402")
      (fields
        (field (name "TOLERANCE") "1%")
        (field (name "POWER") "1/8W")
        (field (name "PACKAGE / CASE") "0402")
      )
      (libsource (lib "Symbols") (part "RESISTOR"))
    )
    (comp (ref "R37")
      (value "40R2")
      (footprint "RES_0402")
      (fields
        (field (name "TOLERANCE") "1%")
        (field (name "POWER") "1/8W")
        (field (name "PACKAGE / CASE") "0402")
      )
      (libsource (lib "Symbols") (part "RESISTOR"))
    )
    (comp (ref "R38")
      (value "40R2")
      (footprint "RES_0402")
      (fields
        (field (name "TOLERANCE") "1%")
        (field (name "POWER") "1/8W")
        (field (name "PACKAGE / CASE") "0402")
      )
      (libsource (lib "Symbols") (part "RESISTOR"))
    )
    (comp (ref "R39")
      (value "40R2")
      (footprint "RES_0402")
      (fields
        (field (name "TOLERANCE") "1%")
        (field (name "POWER") "1/8W")
        (field (name "PACKAGE / CASE") "0402")
      )
      (libsource (lib "Symbols") (part "RESISTOR"))
    )
    (comp (ref "R40")
      (value "40R2")
      (footprint "RES_0402")
      (fields
        (field (name "TOLERANCE") "1%")
        (field (name "POWER") "1/8W")
        (field (name "PACKAGE / CASE") "0402")
      )
      (libsource (lib "Symbols") (part "RESISTOR"))
    )
    (comp (ref "R41")
      (value "40R2")
      (footprint "RES_0402")
      (fields
        (field (name "TOLERANCE") "1%")
        (field (name "POWER") "1/8W")
        (field (name "PACKAGE / CASE") "0402")
      )
      (libsource (lib "Symbols") (part "RESISTOR"))
    )
    (comp (ref "R42")
      (value "40R2")
      (footprint "RES_0402")
      (fields
        (field (name "TOLERANCE") "1%")
        (field (name "POWER") "1/8W")
        (field (name "PACKAGE / CASE") "0402")
      )
      (libsource (lib "Symbols") (part "RESISTOR"))
    )
    (comp (ref "R43")
      (value "40R2")
      (footprint "RES_0402")
      (fields
        (field (name "TOLERANCE") "1%")
        (field (name "POWER") "1/8W")
        (field (name "PACKAGE / CASE") "0402")
      )
      (libsource (lib "Symbols") (part "RESISTOR"))
    )
    (comp (ref "R44")
      (value "40R2")
      (footprint "RES_0402")
      (fields
        (field (name "TOLERANCE") "1%")
        (field (name "POWER") "1/8W")
        (field (name "PACKAGE / CASE") "0402")
      )
      (libsource (lib "Symbols") (part "RESISTOR"))
    )
    (comp (ref "U1")
      (value "MT41K512M16HA-125 :A")
      (footprint "FBGA-96")
      (description "DRAM 8G 1.35V 512Mx16 800 MHz DDR3 0C-90C")
      (fields
        (field (name "MFR") "Alliance Memory")
        (field (name "SUPPLIER PART NUMBER 1") "913-41K512M16HA125A")
      )
      (libsource (lib "CryptLib") (part "IC_MT41K512M16HA-125"))
    )
  )
  (nets
    (net (code "2") (name "+DDR_VREF") (class "Default")
      (node (ref "U1") (pin "H1") (pinfunction "VREFDQ_H1") (pintype "power_in"))
      (node (ref "U1") (pin "M8") (pinfunction "VREFCA_M8") (pintype "power_in"))
    )
    (net (code "3") (name "+VDDR") (class "Default")
      (node (ref "C10") (pin "1") (pinfunction "1_1") (pintype "passive"))
      (node (ref "C11") (pin "1") (pinfunction "1_1") (pintype "passive"))
      (node (ref "C12") (pin "1") (pinfunction "1_1") (pintype "passive"))
      (node (ref "C13") (pin "1") (pinfunction "1_1") (pintype "passive"))
      (node (ref "C14") (pin "1") (pinfunction "1_1") (pintype "passive"))
      (node (ref "C15") (pin "1") (pinfunction "1_1") (pintype "passive"))
      (node (ref "C16") (pin "1") (pinfunction "1_1") (pintype "passive"))
      (node (ref "C17") (pin "1") (pinfunction "1_1") (pintype "passive"))
      (node (ref "C18") (pin "1") (pinfunction "1_1") (pintype "passive"))
      (node (ref "C19") (pin "1") (pinfunction "1_1") (pintype "passive"))
      (node (ref "C20") (pin "1") (pinfunction "1_1") (pintype "passive"))
      (node (ref "C21") (pin "1") (pinfunction "1_1") (pintype "passive"))
      (node (ref "C22") (pin "1") (pinfunction "1_1") (pintype "passive"))
      (node (ref "C23") (pin "1") (pinfunction "1_1") (pintype "passive"))
      (node (ref "C24") (pin "1") (pinfunction "1_1") (pintype "passive"))
      (node (ref "C25") (pin "1") (pinfunction "1_1") (pintype "passive"))
      (node (ref "C26") (pin "1") (pinfunction "1_1") (pintype "passive"))
      (node (ref "C27") (pin "1") (pinfunction "1_1") (pintype "passive"))
      (node (ref "C28") (pin "1") (pinfunction "1_1") (pintype "passive"))
      (node (ref "C29") (pin "1") (pinfunction "1_1") (pintype "passive"))
      (node (ref "C30") (pin "1") (pinfunction "1_1") (pintype "passive"))
      (node (ref "C31") (pin "1") (pinfunction "1_1") (pintype "passive"))
      (node (ref "C32") (pin "1") (pinfunction "1_1") (pintype "passive"))
      (node (ref "C33") (pin "1") (pinfunction "1_1") (pintype "passive"))
      (node (ref "C34") (pin "1") (pinfunction "1_1") (pintype "passive"))
      (node (ref "C35") (pin "1") (pinfunction "1_1") (pintype "passive"))
      (node (ref "C36") (pin "1") (pinfunction "1_1") (pintype "passive"))
      (node (ref "C37") (pin "1") (pinfunction "1_1") (pintype "passive"))
      (node (ref "C38") (pin "1") (pinfunction "1_1") (pintype "passive"))
      (node (ref "C39") (pin "1") (pinfunction "1_1") (pintype "passive"))
      (node (ref "C40") (pin "1") (pinfunction "1_1") (pintype "passive"))
      (node (ref "C41") (pin "1") (pinfunction "1_1") (pintype "passive"))
      (node (ref "C42") (pin "1") (pinfunction "1_1") (pintype "passive"))
      (node (ref "C43") (pin "1") (pinfunction "1_1") (pintype "passive"))
      (node (ref "C44") (pin "1") (pinfunction "1_1") (pintype "passive"))
      (node (ref "C45") (pin "1") (pinfunction "1_1") (pintype "passive"))
      (node (ref "C46") (pin "1") (pinfunction "1_1") (pintype "passive"))
      (node (ref "C47") (pin "1") (pinfunction "1_1") (pintype "passive"))
      (node (ref "C48") (pin "1") (pinfunction "1_1") (pintype "passive"))
      (node (ref "C49") (pin "1") (pinfunction "1_1") (pintype "passive"))
      (node (ref "C5") (pin "1") (pinfunction "1_1") (pintype "passive"))
      (node (ref "C50") (pin "1") (pinfunction "1_1") (pintype "passive"))
      (node (ref "C51") (pin "1") (pinfunction "1_1") (pintype "passive"))
      (node (ref "C52") (pin "1") (pinfunction "1_1") (pintype "passive"))
      (node (ref "C53") (pin "1") (pinfunction "1_1") (pintype "passive"))
      (node (ref "C54") (pin "1") (pinfunction "1_1") (pintype "passive"))
      (node (ref "C55") (pin "1") (pinfunction "1_1") (pintype "passive"))
      (node (ref "C56") (pin "1") (pinfunction "1_1") (pintype "passive"))
      (node (ref "C57") (pin "1") (pinfunction "1_1") (pintype "passive"))
      (node (ref "C58") (pin "1") (pinfunction "1_1") (pintype "passive"))
      (node (ref "C59") (pin "1") (pinfunction "1_1") (pintype "passive"))
      (node (ref "C6") (pin "1") (pinfunction "1_1") (pintype "passive"))
      (node (ref "C60") (pin "1") (pinfunction "1_1") (pintype "passive"))
      (node (ref "C61") (pin "1") (pinfunction "1_1") (pintype "passive"))
      (node (ref "C62") (pin "1") (pinfunction "1_1") (pintype "passive"))
      (node (ref "C63") (pin "1") (pinfunction "1_1") (pintype "passive"))
      (node (ref "C64") (pin "1") (pinfunction "1_1") (pintype "passive"))
      (node (ref "C65") (pin "1") (pinfunction "1_1") (pintype "passive"))
      (node (ref "C66") (pin "1") (pinfunction "1_1") (pintype "passive"))
      (node (ref "C7") (pin "1") (pinfunction "1_1") (pintype "passive"))
      (node (ref "C8") (pin "1") (pinfunction "1_1") (pintype "passive"))
      (node (ref "C87") (pin "2") (pinfunction "2_2") (pintype "passive"))
      (node (ref "C89") (pin "2") (pinfunction "2_2") (pintype "passive"))
      (node (ref "C9") (pin "1") (pinfunction "1_1") (pintype "passive"))
      (node (ref "C90") (pin "2") (pinfunction "2_2") (pintype "passive"))
      (node (ref "U1") (pin "A1") (pinfunction "VDDQ@1_A1") (pintype "power_in"))
      (node (ref "U1") (pin "A8") (pinfunction "VDDQ@2_A8") (pintype "power_in"))
      (node (ref "U1") (pin "B2") (pinfunction "VDD@1_B2") (pintype "power_in"))
      (node (ref "U1") (pin "C1") (pinfunction "VDDQ@3_C1") (pintype "power_in"))
      (node (ref "U1") (pin "C9") (pinfunction "VDDQ@4_C9") (pintype "power_in"))
      (node (ref "U1") (pin "D2") (pinfunction "VDDQ@5_D2") (pintype "power_in"))
      (node (ref "U1") (pin "D9") (pinfunction "VDD@2_D9") (pintype "power_in"))
      (node (ref "U1") (pin "E9") (pinfunction "VDDQ@6_E9") (pintype "power_in"))
      (node (ref "U1") (pin "F1") (pinfunction "VDDQ@7_F1") (pintype "power_in"))
      (node (ref "U1") (pin "G7") (pinfunction "VDD@3_G7") (pintype "power_in"))
      (node (ref "U1") (pin "H2") (pinfunction "VDDQ@8_H2") (pintype "power_in"))
      (node (ref "U1") (pin "H9") (pinfunction "VDDQ@9_H9") (pintype "power_in"))
      (node (ref "U1") (pin "K2") (pinfunction "VDD@4_K2") (pintype "power_in"))
      (node (ref "U1") (pin "K8") (pinfunction "VDD@5_K8") (pintype "power_in"))
      (node (ref "U1") (pin "N1") (pinfunction "VDD@6_N1") (pintype "power_in"))
      (node (ref "U1") (pin "N9") (pinfunction "VDD@7_N9") (pintype "power_in"))
      (node (ref "U1") (pin "R1") (pinfunction "VDD@8_R1") (pintype "power_in"))
      (node (ref "U1") (pin "R9") (pinfunction "VDD@9_R9") (pintype "power_in"))
    )
    (net (code "4") (name "+VTT") (class "Default")
      (node (ref "C67") (pin "1") (pinfunction "1_1") (pintype "passive"))
      (node (ref "C68") (pin "1") (pinfunction "1_1") (pintype "passive"))
      (node (ref "C69") (pin "1") (pinfunction "1_1") (pintype "passive"))
      (node (ref "C70") (pin "1") (pinfunction "1_1") (pintype "passive"))
      (node (ref "C71") (pin "1") (pinfunction "1_1") (pintype "passive"))
      (node (ref "C72") (pin "1") (pinfunction "1_1") (pintype "passive"))
      (node (ref "C73") (pin "1") (pinfunction "1_1") (pintype "passive"))
      (node (ref "C74") (pin "1") (pinfunction "1_1") (pintype "passive"))
      (node (ref "C75") (pin "1") (pinfunction "1_1") (pintype "passive"))
      (node (ref "C76") (pin "1") (pinfunction "1_1") (pintype "passive"))
      (node (ref "C77") (pin "1") (pinfunction "1_1") (pintype "passive"))
      (node (ref "C78") (pin "1") (pinfunction "1_1") (pintype "passive"))
      (node (ref "C79") (pin "1") (pinfunction "1_1") (pintype "passive"))
      (node (ref "C80") (pin "1") (pinfunction "1_1") (pintype "passive"))
      (node (ref "C81") (pin "1") (pinfunction "1_1") (pintype "passive"))
      (node (ref "C82") (pin "1") (pinfunction "1_1") (pintype "passive"))
      (node (ref "C83") (pin "1") (pinfunction "1_1") (pintype "passive"))
      (node (ref "C84") (pin "1") (pinfunction "1_1") (pintype "passive"))
      (node (ref "C85") (pin "1") (pinfunction "1_1") (pintype "passive"))
      (node (ref "C86") (pin "1") (pinfunction "1_1") (pintype "passive"))
      (node (ref "C87") (pin "1") (pinfunction "1_1") (pintype "passive"))
      (node (ref "C88") (pin "1") (pinfunction "1_1") (pintype "passive"))
      (node (ref "C89") (pin "1") (pinfunction "1_1") (pintype "passive"))
      (node (ref "C90") (pin "1") (pinfunction "1_1") (pintype "passive"))
      (node (ref "C91") (pin "1") (pinfunction "1_1") (pintype "passive"))
      (node (ref "C92") (pin "1") (pinfunction "1_1") (pintype "passive"))
      (node (ref "C93") (pin "2") (pinfunction "2_2") (pintype "passive"))
      (node (ref "C94") (pin "1") (pinfunction "1_1") (pintype "passive"))
      (node (ref "C95") (pin "1") (pinfunction "1_1") (pintype "passive"))
      (node (ref "C96") (pin "1") (pinfunction "1_1") (pintype "passive"))
      (node (ref "C97") (pin "1") (pinfunction "1_1") (pintype "passive"))
      (node (ref "C98") (pin "1") (pinfunction "1_1") (pintype "passive"))
      (node (ref "R15") (pin "2") (pinfunction "2_2") (pintype "passive"))
      (node (ref "R16") (pin "2") (pinfunction "2_2") (pintype "passive"))
      (node (ref "R17") (pin "2") (pinfunction "2_2") (pintype "passive"))
      (node (ref "R18") (pin "2") (pinfunction "2_2") (pintype "passive"))
      (node (ref "R19") (pin "2") (pinfunction "2_2") (pintype "passive"))
      (node (ref "R20") (pin "2") (pinfunction "2_2") (pintype "passive"))
      (node (ref "R21") (pin "2") (pinfunction "2_2") (pintype "passive"))
      (node (ref "R22") (pin "2") (pinfunction "2_2") (pintype "passive"))
      (node (ref "R23") (pin "2") (pinfunction "2_2") (pintype "passive"))
      (node (ref "R24") (pin "2") (pinfunction "2_2") (pintype "passive"))
      (node (ref "R25") (pin "2") (pinfunction "2_2") (pintype "passive"))
      (node (ref "R26") (pin "2") (pinfunction "2_2") (pintype "passive"))
      (node (ref "R27") (pin "2") (pinfunction "2_2") (pintype "passive"))
      (node (ref "R28") (pin "2") (pinfunction "2_2") (pintype "passive"))
      (node (ref "R29") (pin "2") (pinfunction "2_2") (pintype "passive"))
      (node (ref "R30") (pin "2") (pinfunction "2_2") (pintype "passive"))
      (node (ref "R31") (pin "2") (pinfunction "2_2") (pintype "passive"))
      (node (ref "R32") (pin "2") (pinfunction "2_2") (pintype "passive"))
      (node (ref "R34") (pin "2") (pinfunction "2_2") (pintype "passive"))
      (node (ref "R35") (pin "2") (pinfunction "2_2") (pintype "passive"))
      (node (ref "R36") (pin "2") (pinfunction "2_2") (pintype "passive"))
      (node (ref "R38") (pin "2") (pinfunction "2_2") (pintype "passive"))
      (node (ref "R39") (pin "2") (pinfunction "2_2") (pintype "passive"))
      (node (ref "R40") (pin "2") (pinfunction "2_2") (pintype "passive"))
      (node (ref "R41") (pin "2") (pinfunction "2_2") (pintype "passive"))
      (node (ref "R43") (pin "2") (pinfunction "2_2") (pintype "passive"))
      (node (ref "R44") (pin "2") (pinfunction "2_2") (pintype "passive"))
    )
    (net (code "5") (name "/A0") (class "Default")
      (node (ref "NT1") (pin "2") (pinfunction "2_2") (pintype "passive"))
      (node (ref "U1") (pin "N3") (pinfunction "A0_N3") (pintype "input"))
    )
    (net (code "6") (name "/A1") (class "Default")
      (node (ref "NT3") (pin "2") (pinfunction "2_2") (pintype "passive"))
      (node (ref "U1") (pin "P7") (pinfunction "A1_P7") (pintype "input"))
    )
    (net (code "7") (name "/A2") (class "Default")
      (node (ref "NT5") (pin "2") (pinfunction "2_2") (pintype "passive"))
      (node (ref "U1") (pin "P3") (pinfunction "A2_P3") (pintype "input"))
    )
    (net (code "8") (name "/A3") (class "Default")
      (node (ref "NT7") (pin "2") (pinfunction "2_2") (pintype "passive"))
      (node (ref "U1") (pin "N2") (pinfunction "A3_N2") (pintype "input"))
    )
    (net (code "9") (name "/A4") (class "Default")
      (node (ref "NT9") (pin "2") (pinfunction "2_2") (pintype "passive"))
      (node (ref "U1") (pin "P8") (pinfunction "A4_P8") (pintype "input"))
    )
    (net (code "10") (name "/A5") (class "Default")
      (node (ref "NT11") (pin "2") (pinfunction "2_2") (pintype "passive"))
      (node (ref "U1") (pin "P2") (pinfunction "A5_P2") (pintype "input"))
    )
    (net (code "11") (name "/A6") (class "Default")
      (node (ref "NT13") (pin "2") (pinfunction "2_2") (pintype "passive"))
      (node (ref "U1") (pin "R8") (pinfunction "A6_R8") (pintype "input"))
    )
    (net (code "12") (name "/A7") (class "Default")
      (node (ref "NT15") (pin "2") (pinfunction "2_2") (pintype "passive"))
      (node (ref "U1") (pin "R2") (pinfunction "A7_R2") (pintype "input"))
    )
    (net (code "13") (name "/A8") (class "Default")
      (node (ref "NT17") (pin "2") (pinfunction "2_2") (pintype "passive"))
      (node (ref "U1") (pin "T8") (pinfunction "A8_T8") (pintype "input"))
    )
    (net (code "14") (name "/A9") (class "Default")
      (node (ref "NT19") (pin "2") (pinfunction "2_2") (pintype "passive"))
      (node (ref "U1") (pin "R3") (pinfunction "A9_R3") (pintype "input"))
    )
    (net (code "15") (name "/A10") (class "Default")
      (node (ref "NT20") (pin "2") (pinfunction "2_2") (pintype "passive"))
      (node (ref "U1") (pin "L7") (pinfunction "A10/AP_L7") (pintype "input"))
    )
    (net (code "16") (name "/A11") (class "Default")
      (node (ref "NT21") (pin "2") (pinfunction "2_2") (pintype "passive"))
      (node (ref "U1") (pin "R7") (pinfunction "A11_R7") (pintype "input"))
    )
    (net (code "17") (name "/A12") (class "Default")
      (node (ref "NT22") (pin "2") (pinfunction "2_2") (pintype "passive"))
      (node (ref "U1") (pin "N7") (pinfunction "A12/!BC_N7") (pintype "input"))
    )
    (net (code "18") (name "/A13") (class "Default")
      (node (ref "NT25") (pin "2") (pinfunction "2_2") (pintype "passive"))
      (node (ref "U1") (pin "T3") (pinfunction "A13_T3") (pintype "input"))
    )
    (net (code "19") (name "/A14") (class "Default")
      (node (ref "NT28") (pin "2") (pinfunction "2_2") (pintype "passive"))
      (node (ref "U1") (pin "T7") (pinfunction "A14_T7") (pintype "input"))
    )
    (net (code "21") (name "/BA0") (class "Default")
      (node (ref "NT23") (pin "2") (pinfunction "2_2") (pintype "passive"))
      (node (ref "U1") (pin "M2") (pinfunction "BA0_M2") (pintype "input"))
    )
    (net (code "22") (name "/BA1") (class "Default")
      (node (ref "NT26") (pin "2") (pinfunction "2_2") (pintype "passive"))
      (node (ref "U1") (pin "N8") (pinfunction "BA1_N8") (pintype "input"))
    )
    (net (code "23") (name "/BA2") (class "Default")
      (node (ref "NT29") (pin "2") (pinfunction "2_2") (pintype "passive"))
      (node (ref "U1") (pin "M3") (pinfunction "BA2_M3") (pintype "input"))
    )
    (net (code "25") (name "/CAS") (class "Default")
      (node (ref "NT8") (pin "2") (pinfunction "2_2") (pintype "passive"))
      (node (ref "U1") (pin "K3") (pinfunction "~{CAS}_K3") (pintype "input"))
    )
    (net (code "26") (name "/CKE") (class "Default")
      (node (ref "NT2") (pin "2") (pinfunction "2_2") (pintype "passive"))
      (node (ref "U1") (pin "K9") (pinfunction "CKE_K9") (pintype "input"))
    )
    (net (code "27") (name "/CK_N") (class "Default")
      (node (ref "NT27") (pin "2") (pinfunction "2_2") (pintype "passive"))
      (node (ref "U1") (pin "K7") (pinfunction "~{CK}_K7") (pintype "input"))
    )
    (net (code "28") (name "/CK_P") (class "Default")
      (node (ref "NT24") (pin "2") (pinfunction "2_2") (pintype "passive"))
      (node (ref "U1") (pin "J7") (pinfunction "CK_J7") (pintype "input"))
    )
    (net (code "29") (name "/CK_TERM_N") (class "Default")
      (node (ref "NT27") (pin "1") (pinfunction "1_1") (pintype "passive"))
      (node (ref "R42") (pin "1") (pinfunction "1_1") (pintype "passive"))
    )
    (net (code "30") (name "/CK_TERM_P") (class "Default")
      (node (ref "NT24") (pin "1") (pinfunction "1_1") (pintype "passive"))
      (node (ref "R37") (pin "1") (pinfunction "1_1") (pintype "passive"))
    )
    (net (code "31") (name "/DDR_CS") (class "Default")
      (node (ref "NT4") (pin "2") (pinfunction "2_2") (pintype "passive"))
      (node (ref "U1") (pin "L2") (pinfunction "~{CS}_L2") (pintype "input"))
    )
    (net (code "32") (name "/DDR_RESET") (class "Default")
      (node (ref "NT18") (pin "2") (pinfunction "2_2") (pintype "passive"))
      (node (ref "U1") (pin "T2") (pinfunction "~{RESET}_T2") (pintype "input"))
    )
    (net (code "33") (name "/DQ0") (class "Default")
      (node (ref "U1") (pin "E3") (pinfunction "DQ0_E3") (pintype "input"))
    )
    (net (code "34") (name "/DQ1") (class "Default")
      (node (ref "U1") (pin "F7") (pinfunction "DQ1_F7") (pintype "input"))
    )
    (net (code "35") (name "/DQ2") (class "Default")
      (node (ref "U1") (pin "F2") (pinfunction "DQ2_F2") (pintype "input"))
    )
    (net (code "36") (name "/DQ3") (class "Default")
      (node (ref "U1") (pin "F8") (pinfunction "DQ3_F8") (pintype "input"))
    )
    (net (code "37") (name "/DQ4") (class "Default")
      (node (ref "U1") (pin "H3") (pinfunction "DQ4_H3") (pintype "input"))
    )
    (net (code "38") (name "/DQ5") (class "Default")
      (node (ref "U1") (pin "H8") (pinfunction "DQ5_H8") (pintype "input"))
    )
    (net (code "39") (name "/DQ6") (class "Default")
      (node (ref "U1") (pin "G2") (pinfunction "DQ6_G2") (pintype "input"))
    )
    (net (code "40") (name "/DQ7") (class "Default")
      (node (ref "U1") (pin "H7") (pinfunction "DQ7_H7") (pintype "input"))
    )
    (net (code "41") (name "/DQ8") (class "Default")
      (node (ref "U1") (pin "D7") (pinfunction "DQ8_D7") (pintype "input"))
    )
    (net (code "42") (name "/DQ9") (class "Default")
      (node (ref "U1") (pin "C3") (pinfunction "DQ9_C3") (pintype "input"))
    )
    (net (code "43") (name "/DQ10") (class "Default")
      (node (ref "U1") (pin "C8") (pinfunction "DQ10_C8") (pintype "input"))
    )
    (net (code "44") (name "/DQ11") (class "Default")
      (node (ref "U1") (pin "C2") (pinfunction "DQ11_C2") (pintype "input"))
    )
    (net (code "45") (name "/DQ12") (class "Default")
      (node (ref "U1") (pin "A7") (pinfunction "DQ12_A7") (pintype "input"))
    )
    (net (code "46") (name "/DQ13") (class "Default")
      (node (ref "U1") (pin "A2") (pinfunction "DQ13_A2") (pintype "input"))
    )
    (net (code "47") (name "/DQ14") (class "Default")
      (node (ref "U1") (pin "B8") (pinfunction "DQ14_B8") (pintype "input"))
    )
    (net (code "48") (name "/DQ15") (class "Default")
      (node (ref "U1") (pin "A3") (pinfunction "DQ15_A3") (pintype "input"))
    )
    (net (code "50") (name "/LDM") (class "Default")
      (node (ref "NT16") (pin "2") (pinfunction "2_2") (pintype "passive"))
      (node (ref "U1") (pin "E7") (pinfunction "LDM_E7") (pintype "input"))
    )
    (net (code "51") (name "/LDQS_N") (class "Default")
      (node (ref "U1") (pin "F3") (pinfunction "LDQS_F3") (pintype "input"))
    )
    (net (code "52") (name "/LDQS_P") (class "Default")
      (node (ref "U1") (pin "G3") (pinfunction "~{LDQS}_G3") (pintype "input"))
    )
    (net (code "53") (name "/ODT") (class "Default")
      (node (ref "NT12") (pin "2") (pinfunction "2_2") (pintype "passive"))
      (node (ref "U1") (pin "K1") (pinfunction "ODT_K1") (pintype "input"))
    )
    (net (code "54") (name "/RAS") (class "Default")
      (node (ref "NT6") (pin "2") (pinfunction "2_2") (pintype "passive"))
      (node (ref "U1") (pin "J3") (pinfunction "~{RAS}_J3") (pintype "input"))
    )
    (net (code "55") (name "/UDM") (class "Default")
      (node (ref "NT14") (pin "2") (pinfunction "2_2") (pintype "passive"))
      (node (ref "U1") (pin "D3") (pinfunction "UDM_D3") (pintype "input"))
    )
    (net (code "56") (name "/UDQS_N") (class "Default")
      (node (ref "U1") (pin "C7") (pinfunction "UDQS_C7") (pintype "input"))
    )
    (net (code "57") (name "/UDQS_P") (class "Default")
      (node (ref "U1") (pin "B7") (pinfunction "~{UDQS}_B7") (pintype "input"))
    )
    (net (code "58") (name "/WE") (class "Default")
      (node (ref "NT10") (pin "2") (pinfunction "2_2") (pintype "passive"))
      (node (ref "U1") (pin "L3") (pinfunction "~{WE}_L3") (pintype "input"))
    )
    (net (code "59") (name "/ZQ") (class "Default")
      (node (ref "R13") (pin "2") (pinfunction "2_2") (pintype "passive"))
      (node (ref "U1") (pin "L8") (pinfunction "ZQ_L8") (pintype "passive"))
    )
    (net (code "61") (name "GND") (class "Default")
      (node (ref "C10") (pin "2") (pinfunction "2_2") (pintype "passive"))
      (node (ref "C11") (pin "2") (pinfunction "2_2") (pintype "passive"))
      (node (ref "C12") (pin "2") (pinfunction "2_2") (pintype "passive"))
      (node (ref "C13") (pin "2") (pinfunction "2_2") (pintype "passive"))
      (node (ref "C14") (pin "2") (pinfunction "2_2") (pintype "passive"))
      (node (ref "C15") (pin "2") (pinfunction "2_2") (pintype "passive"))
      (node (ref "C16") (pin "2") (pinfunction "2_2") (pintype "passive"))
      (node (ref "C17") (pin "2") (pinfunction "2_2") (pintype "passive"))
      (node (ref "C18") (pin "2") (pinfunction "2_2") (pintype "passive"))
      (node (ref "C19") (pin "2") (pinfunction "2_2") (pintype "passive"))
      (node (ref "C20") (pin "2") (pinfunction "2_2") (pintype "passive"))
      (node (ref "C21") (pin "2") (pinfunction "2_2") (pintype "passive"))
      (node (ref "C22") (pin "2") (pinfunction "2_2") (pintype "passive"))
      (node (ref "C23") (pin "2") (pinfunction "2_2") (pintype "passive"))
      (node (ref "C24") (pin "2") (pinfunction "2_2") (pintype "passive"))
      (node (ref "C25") (pin "2") (pinfunction "2_2") (pintype "passive"))
      (node (ref "C26") (pin "2") (pinfunction "2_2") (pintype "passive"))
      (node (ref "C27") (pin "2") (pinfunction "2_2") (pintype "passive"))
      (node (ref "C28") (pin "2") (pinfunction "2_2") (pintype "passive"))
      (node (ref "C29") (pin "2") (pinfunction "2_2") (pintype "passive"))
      (node (ref "C30") (pin "2") (pinfunction "2_2") (pintype "passive"))
      (node (ref "C31") (pin "2") (pinfunction "2_2") (pintype "passive"))
      (node (ref "C32") (pin "2") (pinfunction "2_2") (pintype "passive"))
      (node (ref "C33") (pin "2") (pinfunction "2_2") (pintype "passive"))
      (node (ref "C34") (pin "2") (pinfunction "2_2") (pintype "passive"))
      (node (ref "C35") (pin "2") (pinfunction "2_2") (pintype "passive"))
      (node (ref "C36") (pin "2") (pinfunction "2_2") (pintype "passive"))
      (node (ref "C37") (pin "2") (pinfunction "2_2") (pintype "passive"))
      (node (ref "C38") (pin "2") (pinfunction "2_2") (pintype "passive"))
      (node (ref "C39") (pin "2") (pinfunction "2_2") (pintype "passive"))
      (node (ref "C40") (pin "2") (pinfunction "2_2") (pintype "passive"))
      (node (ref "C41") (pin "2") (pinfunction "2_2") (pintype "passive"))
      (node (ref "C42") (pin "2") (pinfunction "2_2") (pintype "passive"))
      (node (ref "C43") (pin "2") (pinfunction "2_2") (pintype "passive"))
      (node (ref "C44") (pin "2") (pinfunction "2_2") (pintype "passive"))
      (node (ref "C45") (pin "2") (pinfunction "2_2") (pintype "passive"))
      (node (ref "C46") (pin "2") (pinfunction "2_2") (pintype "passive"))
      (node (ref "C47") (pin "2") (pinfunction "2_2") (pintype "passive"))
      (node (ref "C48") (pin "2") (pinfunction "2_2") (pintype "passive"))
      (node (ref "C49") (pin "2") (pinfunction "2_2") (pintype "passive"))
      (node (ref "C5") (pin "2") (pinfunction "2_2") (pintype "passive"))
      (node (ref "C50") (pin "2") (pinfunction "2_2") (pintype "passive"))
      (node (ref "C51") (pin "2") (pinfunction "2_2") (pintype "passive"))
      (node (ref "C52") (pin "2") (pinfunction "2_2") (pintype "passive"))
      (node (ref "C53") (pin "2") (pinfunction "2_2") (pintype "passive"))
      (node (ref "C54") (pin "2") (pinfunction "2_2") (pintype "passive"))
      (node (ref "C55") (pin "2") (pinfunction "2_2") (pintype "passive"))
      (node (ref "C56") (pin "2") (pinfunction "2_2") (pintype "passive"))
      (node (ref "C57") (pin "2") (pinfunction "2_2") (pintype "passive"))
      (node (ref "C58") (pin "2") (pinfunction "2_2") (pintype "passive"))
      (node (ref "C59") (pin "2") (pinfunction "2_2") (pintype "passive"))
      (node (ref "C6") (pin "2") (pinfunction "2_2") (pintype "passive"))
      (node (ref "C60") (pin "2") (pinfunction "2_2") (pintype "passive"))
      (node (ref "C61") (pin "2") (pinfunction "2_2") (pintype "passive"))
      (node (ref "C62") (pin "2") (pinfunction "2_2") (pintype "passive"))
      (node (ref "C63") (pin "2") (pinfunction "2_2") (pintype "passive"))
      (node (ref "C64") (pin "2") (pinfunction "2_2") (pintype "passive"))
      (node (ref "C65") (pin "2") (pinfunction "2_2") (pintype "passive"))
      (node (ref "C66") (pin "2") (pinfunction "2_2") (pintype "passive"))
      (node (ref "C67") (pin "2") (pinfunction "2_2") (pintype "passive"))
      (node (ref "C68") (pin "2") (pinfunction "2_2") (pintype "passive"))
      (node (ref "C69") (pin "2") (pinfunction "2_2") (pintype "passive"))
      (node (ref "C7") (pin "2") (pinfunction "2_2") (pintype "passive"))
      (node (ref "C70") (pin "2") (pinfunction "2_2") (pintype "passive"))
      (node (ref "C71") (pin "2") (pinfunction "2_2") (pintype "passive"))
      (node (ref "C72") (pin "2") (pinfunction "2_2") (pintype "passive"))
      (node (ref "C73") (pin "2") (pinfunction "2_2") (pintype "passive"))
      (node (ref "C74") (pin "2") (pinfunction "2_2") (pintype "passive"))
      (node (ref "C75") (pin "2") (pinfunction "2_2") (pintype "passive"))
      (node (ref "C76") (pin "2") (pinfunction "2_2") (pintype "passive"))
      (node (ref "C77") (pin "2") (pinfunction "2_2") (pintype "passive"))
      (node (ref "C78") (pin "2") (pinfunction "2_2") (pintype "passive"))
      (node (ref "C79") (pin "2") (pinfunction "2_2") (pintype "passive"))
      (node (ref "C8") (pin "2") (pinfunction "2_2") (pintype "passive"))
      (node (ref "C80") (pin "2") (pinfunction "2_2") (pintype "passive"))
      (node (ref "C81") (pin "2") (pinfunction "2_2") (pintype "passive"))
      (node (ref "C82") (pin "2") (pinfunction "2_2") (pintype "passive"))
      (node (ref "C83") (pin "2") (pinfunction "2_2") (pintype "passive"))
      (node (ref "C84") (pin "2") (pinfunction "2_2") (pintype "passive"))
      (node (ref "C85") (pin "2") (pinfunction "2_2") (pintype "passive"))
      (node (ref "C86") (pin "2") (pinfunction "2_2") (pintype "passive"))
      (node (ref "C88") (pin "2") (pinfunction "2_2") (pintype "passive"))
      (node (ref "C9") (pin "2") (pinfunction "2_2") (pintype "passive"))
      (node (ref "C91") (pin "2") (pinfunction "2_2") (pintype "passive"))
      (node (ref "C92") (pin "2") (pinfunction "2_2") (pintype "passive"))
      (node (ref "C94") (pin "2") (pinfunction "2_2") (pintype "passive"))
      (node (ref "C95") (pin "2") (pinfunction "2_2") (pintype "passive"))
      (node (ref "C96") (pin "2") (pinfunction "2_2") (pintype "passive"))
      (node (ref "C97") (pin "2") (pinfunction "2_2") (pintype "passive"))
      (node (ref "C98") (pin "2") (pinfunction "2_2") (pintype "passive"))
      (node (ref "HEAT1") (pin "1") (pintype "passive"))
      (node (ref "HEAT1") (pin "2") (pintype "passive"))
      (node (ref "R13") (pin "1") (pinfunction "1_1") (pintype "passive"))
      (node (ref "R14") (pin "2") (pinfunction "2_2") (pintype "passive"))
      (node (ref "R33") (pin "2") (pinfunction "2_2") (pintype "passive"))
      (node (ref "U1") (pin "A9") (pinfunction "VSS@1_A9") (pintype "power_in"))
      (node (ref "U1") (pin "B1") (pinfunction "VSSQ@1_B1") (pintype "power_in"))
      (node (ref "U1") (pin "B3") (pinfunction "VSS@2_B3") (pintype "power_in"))
      (node (ref "U1") (pin "B9") (pinfunction "VSSQ@2_B9") (pintype "power_in"))
      (node (ref "U1") (pin "D1") (pinfunction "VSSQ@3_D1") (pintype "power_in"))
      (node (ref "U1") (pin "D8") (pinfunction "VSSQ@4_D8") (pintype "power_in"))
      (node (ref "U1") (pin "E1") (pinfunction "VSS@3_E1") (pintype "power_in"))
      (node (ref "U1") (pin "E2") (pinfunction "VSSQ@5_E2") (pintype "power_in"))
      (node (ref "U1") (pin "E8") (pinfunction "VSSQ@6_E8") (pintype "power_in"))
      (node (ref "U1") (pin "F9") (pinfunction "VSSQ@7_F9") (pintype "power_in"))
      (node (ref "U1") (pin "G1") (pinfunction "VSSQ@8_G1") (pintype "power_in"))
      (node (ref "U1") (pin "G8") (pinfunction "VSS@4_G8") (pintype "power_in"))
      (node (ref "U1") (pin "G9") (pinfunction "VSSQ@9_G9") (pintype "power_in"))
      (node (ref "U1") (pin "J2") (pinfunction "VSS@5_J2") (pintype "power_in"))
      (node (ref "U1") (pin "J8") (pinfunction "VSS@6_J8") (pintype "power_in"))
      (node (ref "U1") (pin "M1") (pinfunction "VSS@7_M1") (pintype "power_in"))
      (node (ref "U1") (pin "M9") (pinfunction "VSS@8_M9") (pintype "power_in"))
      (node (ref "U1") (pin "P1") (pinfunction "VSS@9_P1") (pintype "power_in"))
      (node (ref "U1") (pin "P9") (pinfunction "VSS@10_P9") (pintype "power_in"))
      (node (ref "U1") (pin "T1") (pinfunction "VSS@11_T1") (pintype "power_in"))
      (node (ref "U1") (pin "T9") (pinfunction "VSS@12_T9") (pintype "power_in"))
    )
    (net (code "62") (name "Net-(C93-Pad1)") (class "Default")
      (node (ref "C93") (pin "1") (pinfunction "1_1") (pintype "passive"))
      (node (ref "R37") (pin "2") (pinfunction "2_2") (pintype "passive"))
      (node (ref "R42") (pin "2") (pinfunction "2_2") (pintype "passive"))
    )
    (net (code "63") (name "Net-(NT1-Pad1)") (class "Default")
      (node (ref "NT1") (pin "1") (pinfunction "1_1") (pintype "passive"))
      (node (ref "R16") (pin "1") (pinfunction "1_1") (pintype "passive"))
    )
    (net (code "64") (name "Net-(NT2-Pad1)") (class "Default")
      (node (ref "NT2") (pin "1") (pinfunction "1_1") (pintype "passive"))
      (node (ref "R14") (pin "1") (pinfunction "1_1") (pintype "passive"))
      (node (ref "R15") (pin "1") (pinfunction "1_1") (pintype "passive"))
    )
    (net (code "65") (name "Net-(NT3-Pad1)") (class "Default")
      (node (ref "NT3") (pin "1") (pinfunction "1_1") (pintype "passive"))
      (node (ref "R17") (pin "1") (pinfunction "1_1") (pintype "passive"))
    )
    (net (code "66") (name "Net-(NT4-Pad1)") (class "Default")
      (node (ref "NT4") (pin "1") (pinfunction "1_1") (pintype "passive"))
      (node (ref "R18") (pin "1") (pinfunction "1_1") (pintype "passive"))
    )
    (net (code "67") (name "Net-(NT5-Pad1)") (class "Default")
      (node (ref "NT5") (pin "1") (pinfunction "1_1") (pintype "passive"))
      (node (ref "R19") (pin "1") (pinfunction "1_1") (pintype "passive"))
    )
    (net (code "68") (name "Net-(NT6-Pad1)") (class "Default")
      (node (ref "NT6") (pin "1") (pinfunction "1_1") (pintype "passive"))
      (node (ref "R20") (pin "1") (pinfunction "1_1") (pintype "passive"))
    )
    (net (code "69") (name "Net-(NT7-Pad1)") (class "Default")
      (node (ref "NT7") (pin "1") (pinfunction "1_1") (pintype "passive"))
      (node (ref "R21") (pin "1") (pinfunction "1_1") (pintype "passive"))
    )
    (net (code "70") (name "Net-(NT8-Pad1)") (class "Default")
      (node (ref "NT8") (pin "1") (pinfunction "1_1") (pintype "passive"))
      (node (ref "R22") (pin "1") (pinfunction "1_1") (pintype "passive"))
    )
    (net (code "71") (name "Net-(NT9-Pad1)") (class "Default")
      (node (ref "NT9") (pin "1") (pinfunction "1_1") (pintype "passive"))
      (node (ref "R23") (pin "1") (pinfunction "1_1") (pintype "passive"))
    )
    (net (code "72") (name "Net-(NT10-Pad1)") (class "Default")
      (node (ref "NT10") (pin "1") (pinfunction "1_1") (pintype "passive"))
      (node (ref "R24") (pin "1") (pinfunction "1_1") (pintype "passive"))
    )
    (net (code "73") (name "Net-(NT11-Pad1)") (class "Default")
      (node (ref "NT11") (pin "1") (pinfunction "1_1") (pintype "passive"))
      (node (ref "R25") (pin "1") (pinfunction "1_1") (pintype "passive"))
    )
    (net (code "74") (name "Net-(NT12-Pad1)") (class "Default")
      (node (ref "NT12") (pin "1") (pinfunction "1_1") (pintype "passive"))
      (node (ref "R26") (pin "1") (pinfunction "1_1") (pintype "passive"))
    )
    (net (code "75") (name "Net-(NT13-Pad1)") (class "Default")
      (node (ref "NT13") (pin "1") (pinfunction "1_1") (pintype "passive"))
      (node (ref "R27") (pin "1") (pinfunction "1_1") (pintype "passive"))
    )
    (net (code "76") (name "Net-(NT14-Pad1)") (class "Default")
      (node (ref "NT14") (pin "1") (pinfunction "1_1") (pintype "passive"))
      (node (ref "R28") (pin "1") (pinfunction "1_1") (pintype "passive"))
    )
    (net (code "77") (name "Net-(NT15-Pad1)") (class "Default")
      (node (ref "NT15") (pin "1") (pinfunction "1_1") (pintype "passive"))
      (node (ref "R29") (pin "1") (pinfunction "1_1") (pintype "passive"))
    )
    (net (code "78") (name "Net-(NT16-Pad1)") (class "Default")
      (node (ref "NT16") (pin "1") (pinfunction "1_1") (pintype "passive"))
      (node (ref "R30") (pin "1") (pinfunction "1_1") (pintype "passive"))
    )
    (net (code "79") (name "Net-(NT17-Pad1)") (class "Default")
      (node (ref "NT17") (pin "1") (pinfunction "1_1") (pintype "passive"))
      (node (ref "R32") (pin "1") (pinfunction "1_1") (pintype "passive"))
    )
    (net (code "80") (name "Net-(NT18-Pad1)") (class "Default")
      (node (ref "NT18") (pin "1") (pinfunction "1_1") (pintype "passive"))
      (node (ref "R31") (pin "1") (pinfunction "1_1") (pintype "passive"))
      (node (ref "R33") (pin "1") (pinfunction "1_1") (pintype "passive"))
    )
    (net (code "81") (name "Net-(NT19-Pad1)") (class "Default")
      (node (ref "NT19") (pin "1") (pinfunction "1_1") (pintype "passive"))
      (node (ref "R34") (pin "1") (pinfunction "1_1") (pintype "passive"))
    )
    (net (code "82") (name "Net-(NT20-Pad1)") (class "Default")
      (node (ref "NT20") (pin "1") (pinfunction "1_1") (pintype "passive"))
      (node (ref "R35") (pin "1") (pinfunction "1_1") (pintype "passive"))
    )
    (net (code "83") (name "Net-(NT21-Pad1)") (class "Default")
      (node (ref "NT21") (pin "1") (pinfunction "1_1") (pintype "passive"))
      (node (ref "R36") (pin "1") (pinfunction "1_1") (pintype "passive"))
    )
    (net (code "84") (name "Net-(NT22-Pad1)") (class "Default")
      (node (ref "NT22") (pin "1") (pinfunction "1_1") (pintype "passive"))
      (node (ref "R38") (pin "1") (pinfunction "1_1") (pintype "passive"))
    )
    (net (code "85") (name "Net-(NT23-Pad1)") (class "Default")
      (node (ref "NT23") (pin "1") (pinfunction "1_1") (pintype "passive"))
      (node (ref "R39") (pin "1") (pinfunction "1_1") (pintype "passive"))
    )
    (net (code "86") (name "Net-(NT25-Pad1)") (class "Default")
      (node (ref "NT25") (pin "1") (pinfunction "1_1") (pintype "passive"))
      (node (ref "R40") (pin "1") (pinfunction "1_1") (pintype "passive"))
    )
    (net (code "87") (name "Net-(NT26-Pad1)") (class "Default")
      (node (ref "NT26") (pin "1") (pinfunction "1_1") (pintype "passive"))
      (node (ref "R41") (pin "1") (pinfunction "1_1") (pintype "passive"))
    )
    (net (code "88") (name "Net-(NT28-Pad1)") (class "Default")
      (node (ref "NT28") (pin "1") (pinfunction "1_1") (pintype "passive"))
      (node (ref "R43") (pin "1") (pinfunction "1_1") (pintype "passive"))
    )
    (net (code "89") (name "Net-(NT29-Pad1)") (class "Default")
      (node (ref "NT29") (pin "1") (pinfunction "1_1") (pintype "passive"))
      (node (ref "R44") (pin "1") (pinfunction "1_1") (pintype "passive"))
    )
    (net (code "90") (name "unconnected-(U1D-NC-PadJ1)") (class "Default")
      (node (ref "U1") (pin "J1") (pinfunction "NC_J1") (pintype "passive+no_connect"))
    )
    (net (code "91") (name "unconnected-(U1D-NC-PadJ9)") (class "Default")
      (node (ref "U1") (pin "J9") (pinfunction "NC_J9") (pintype "passive+no_connect"))
    )
    (net (code "92") (name "unconnected-(U1D-NC-PadL1)") (class "Default")
      (node (ref "U1") (pin "L1") (pinfunction "NC_L1") (pintype "passive+no_connect"))
    )
    (net (code "93") (name "unconnected-(U1D-NC-PadL9)") (class "Default")
      (node (ref "U1") (pin "L9") (pinfunction "NC_L9") (pintype "passive+no_connect"))
    )
    (net (code "94") (name "unconnected-(U1D-NC-PadM7)") (class "Default")
      (node (ref "U1") (pin "M7") (pinfunction "NC_M7") (pintype "passive+no_connect"))
    )
  )
)
